# Drive_Board_2018-19.net
KiCad netlist of a schematic drawn in EAGLE
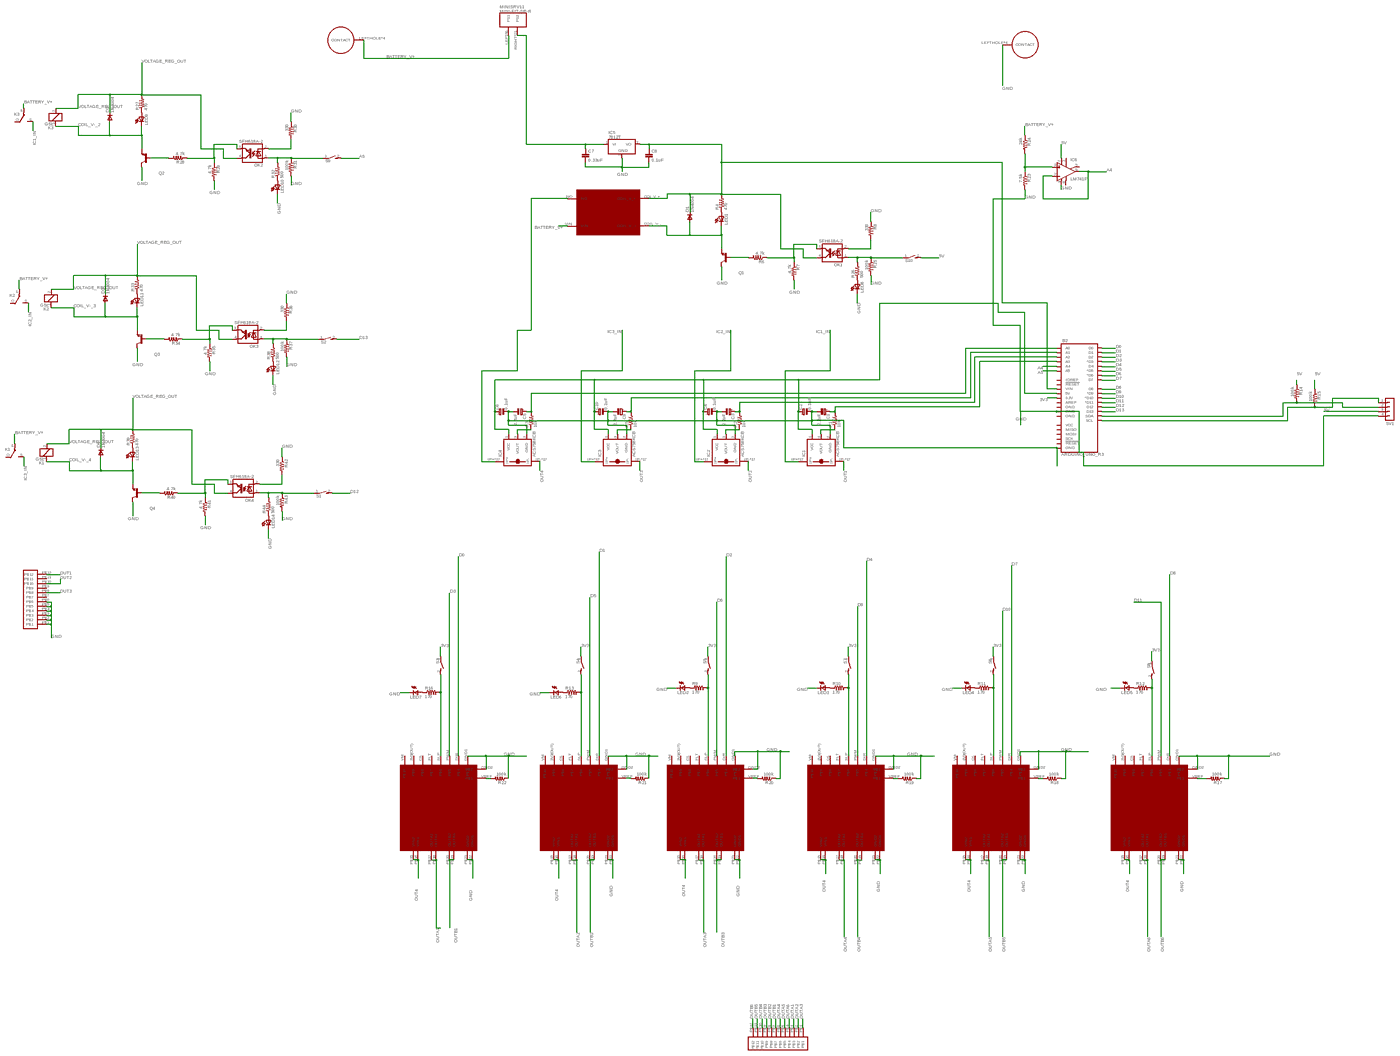
[diagram p0: schematic, sheet 1, overview]
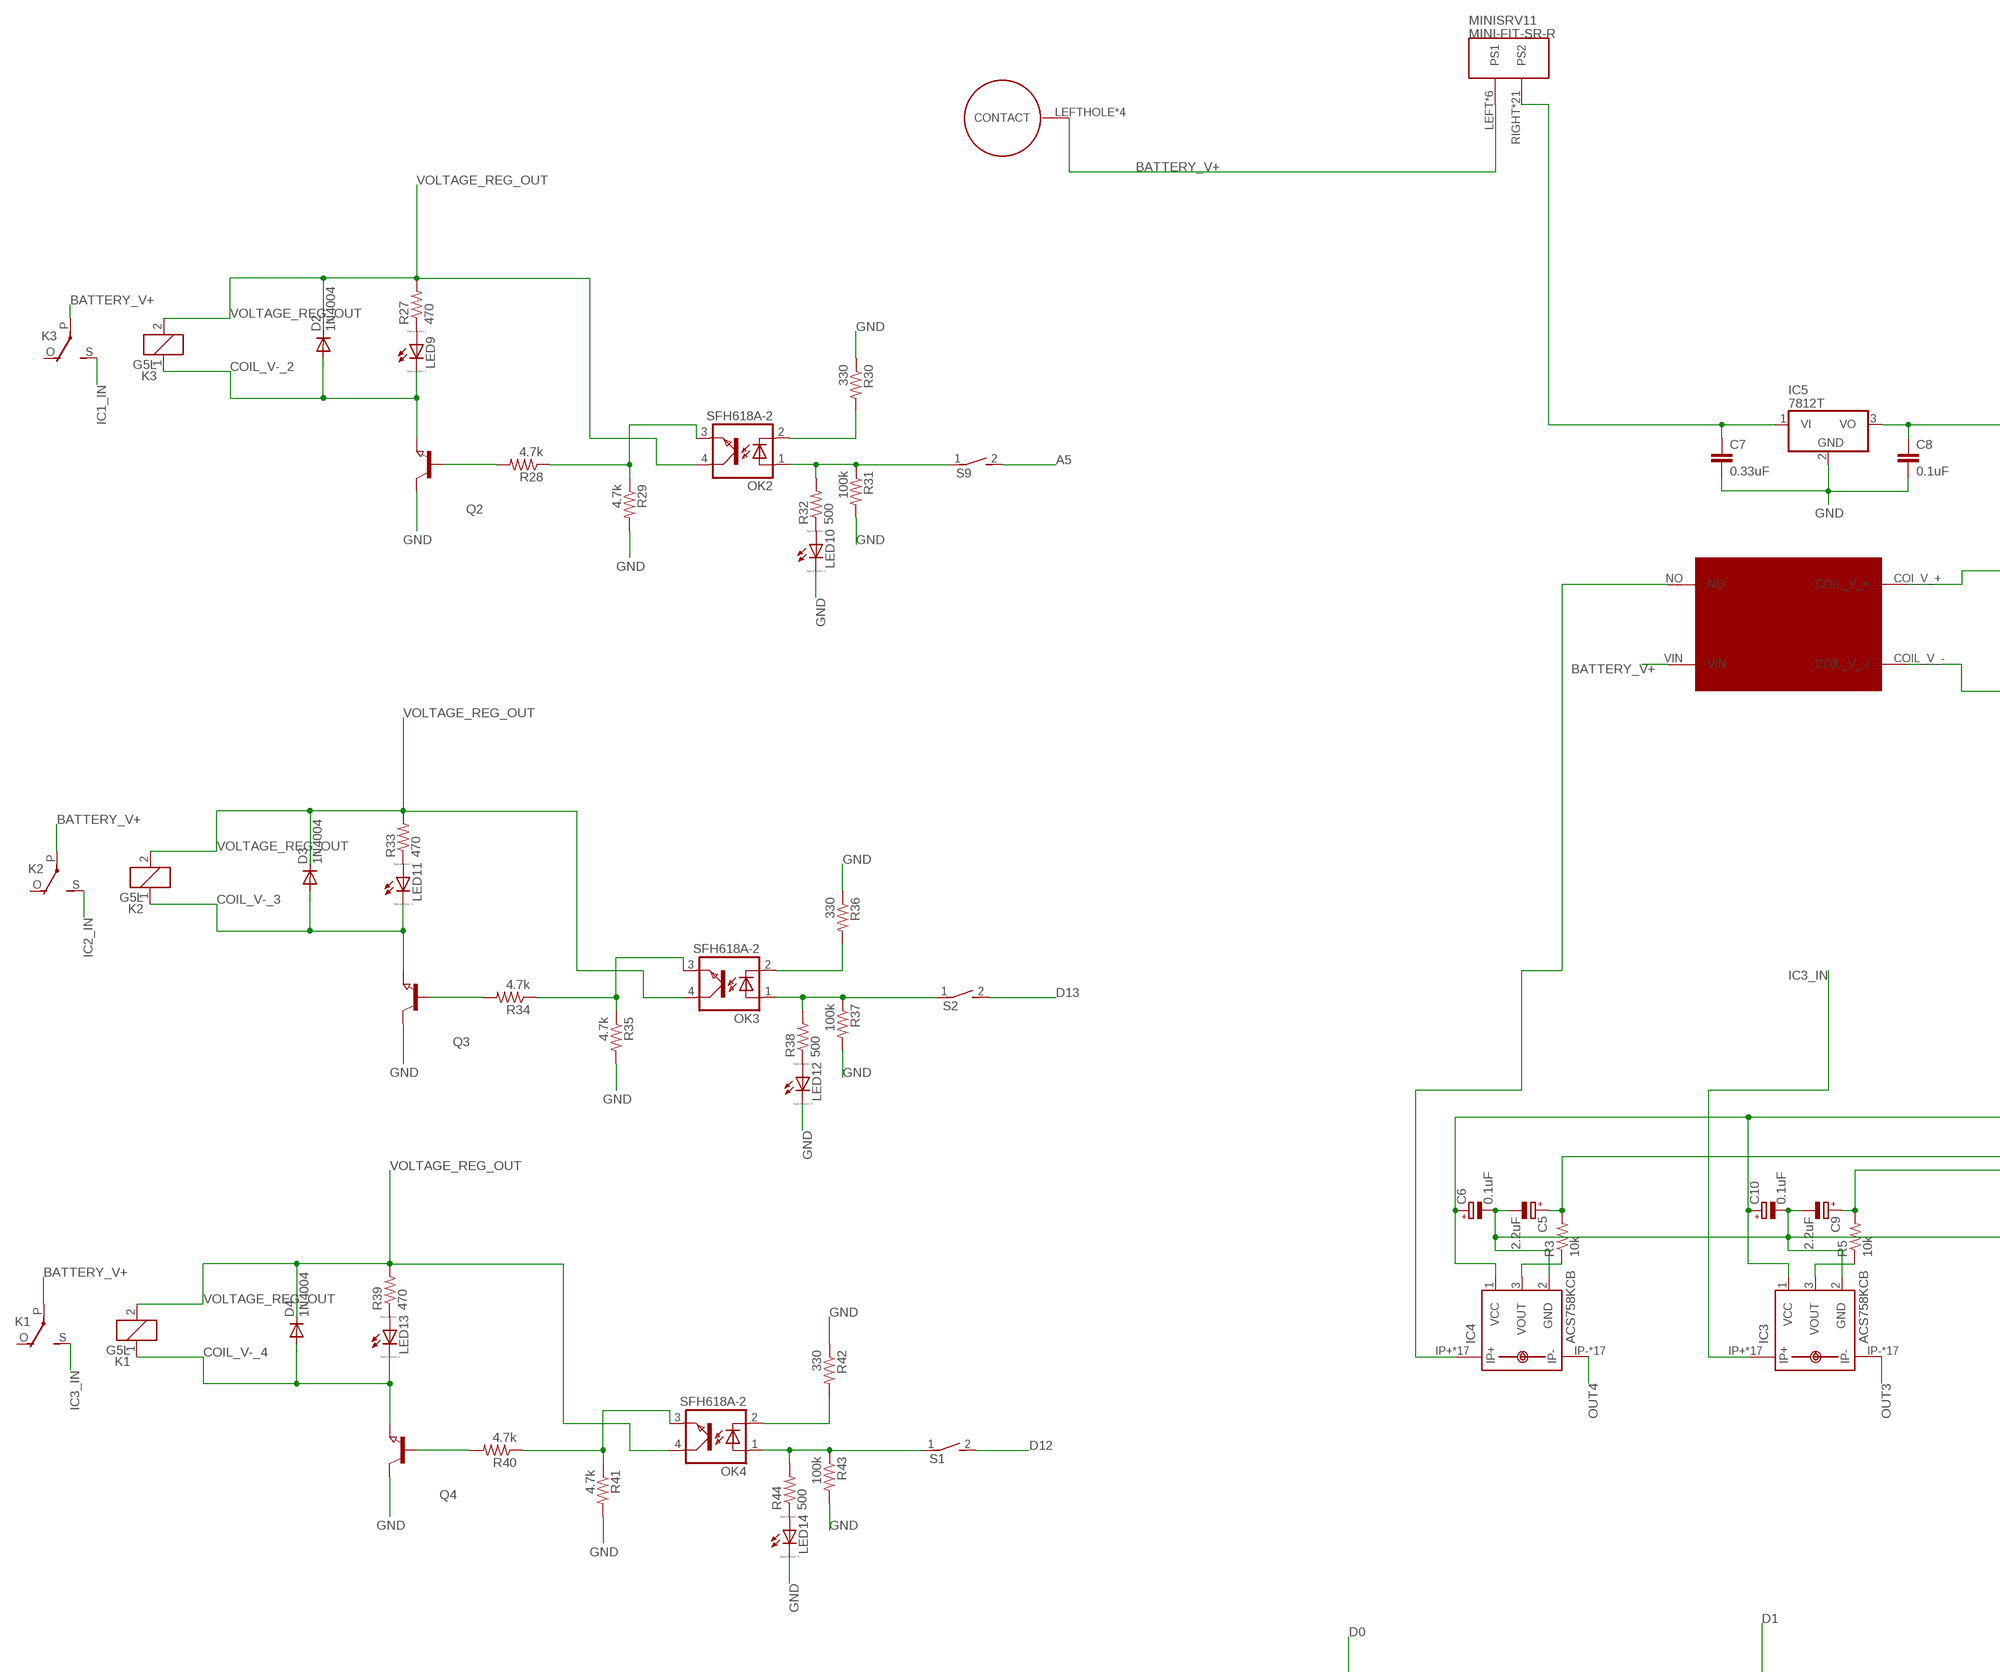
[diagram p1: schematic, sheet 1, part 1 of 4]
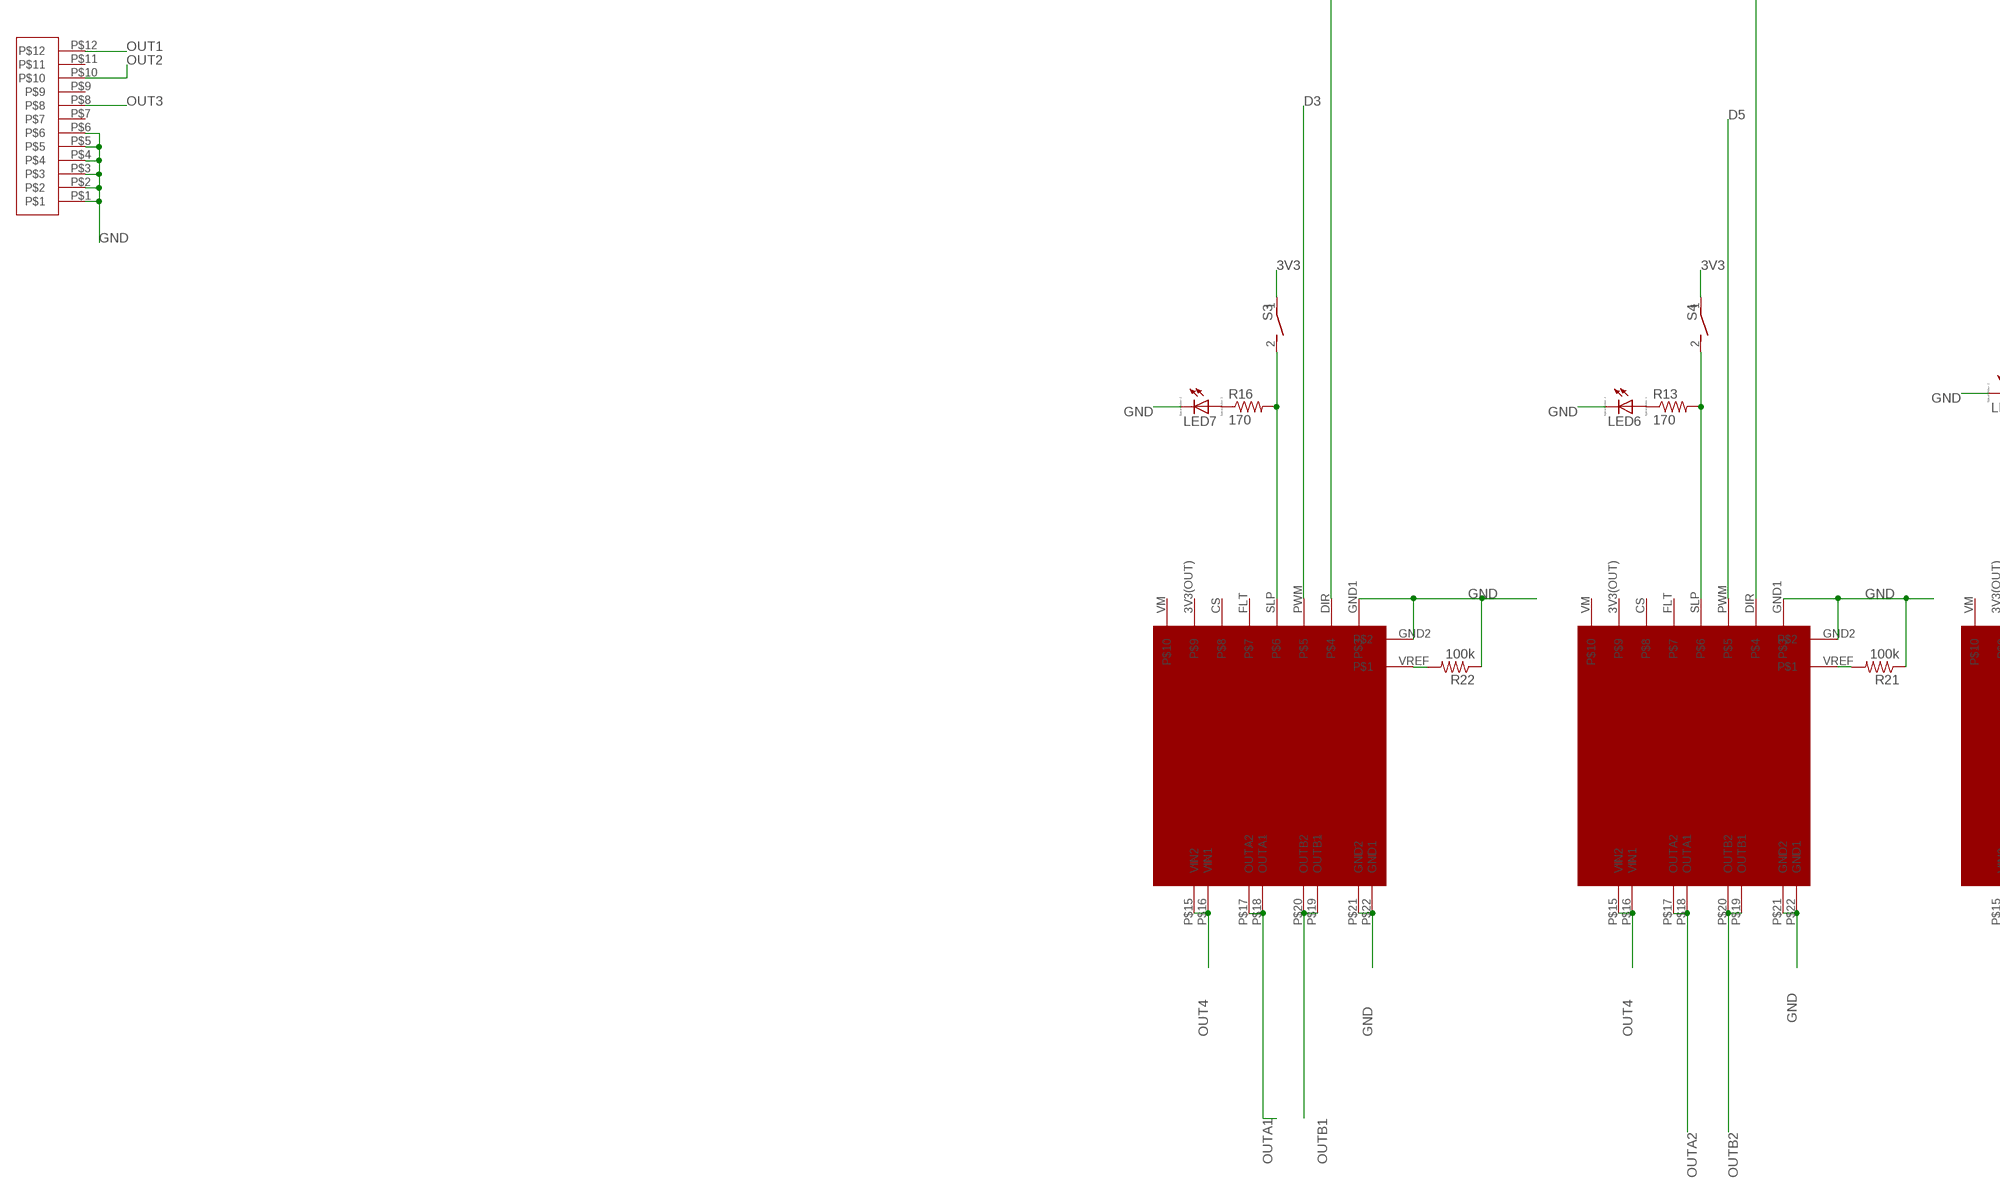
[diagram p2: schematic, sheet 1, part 2 of 4]
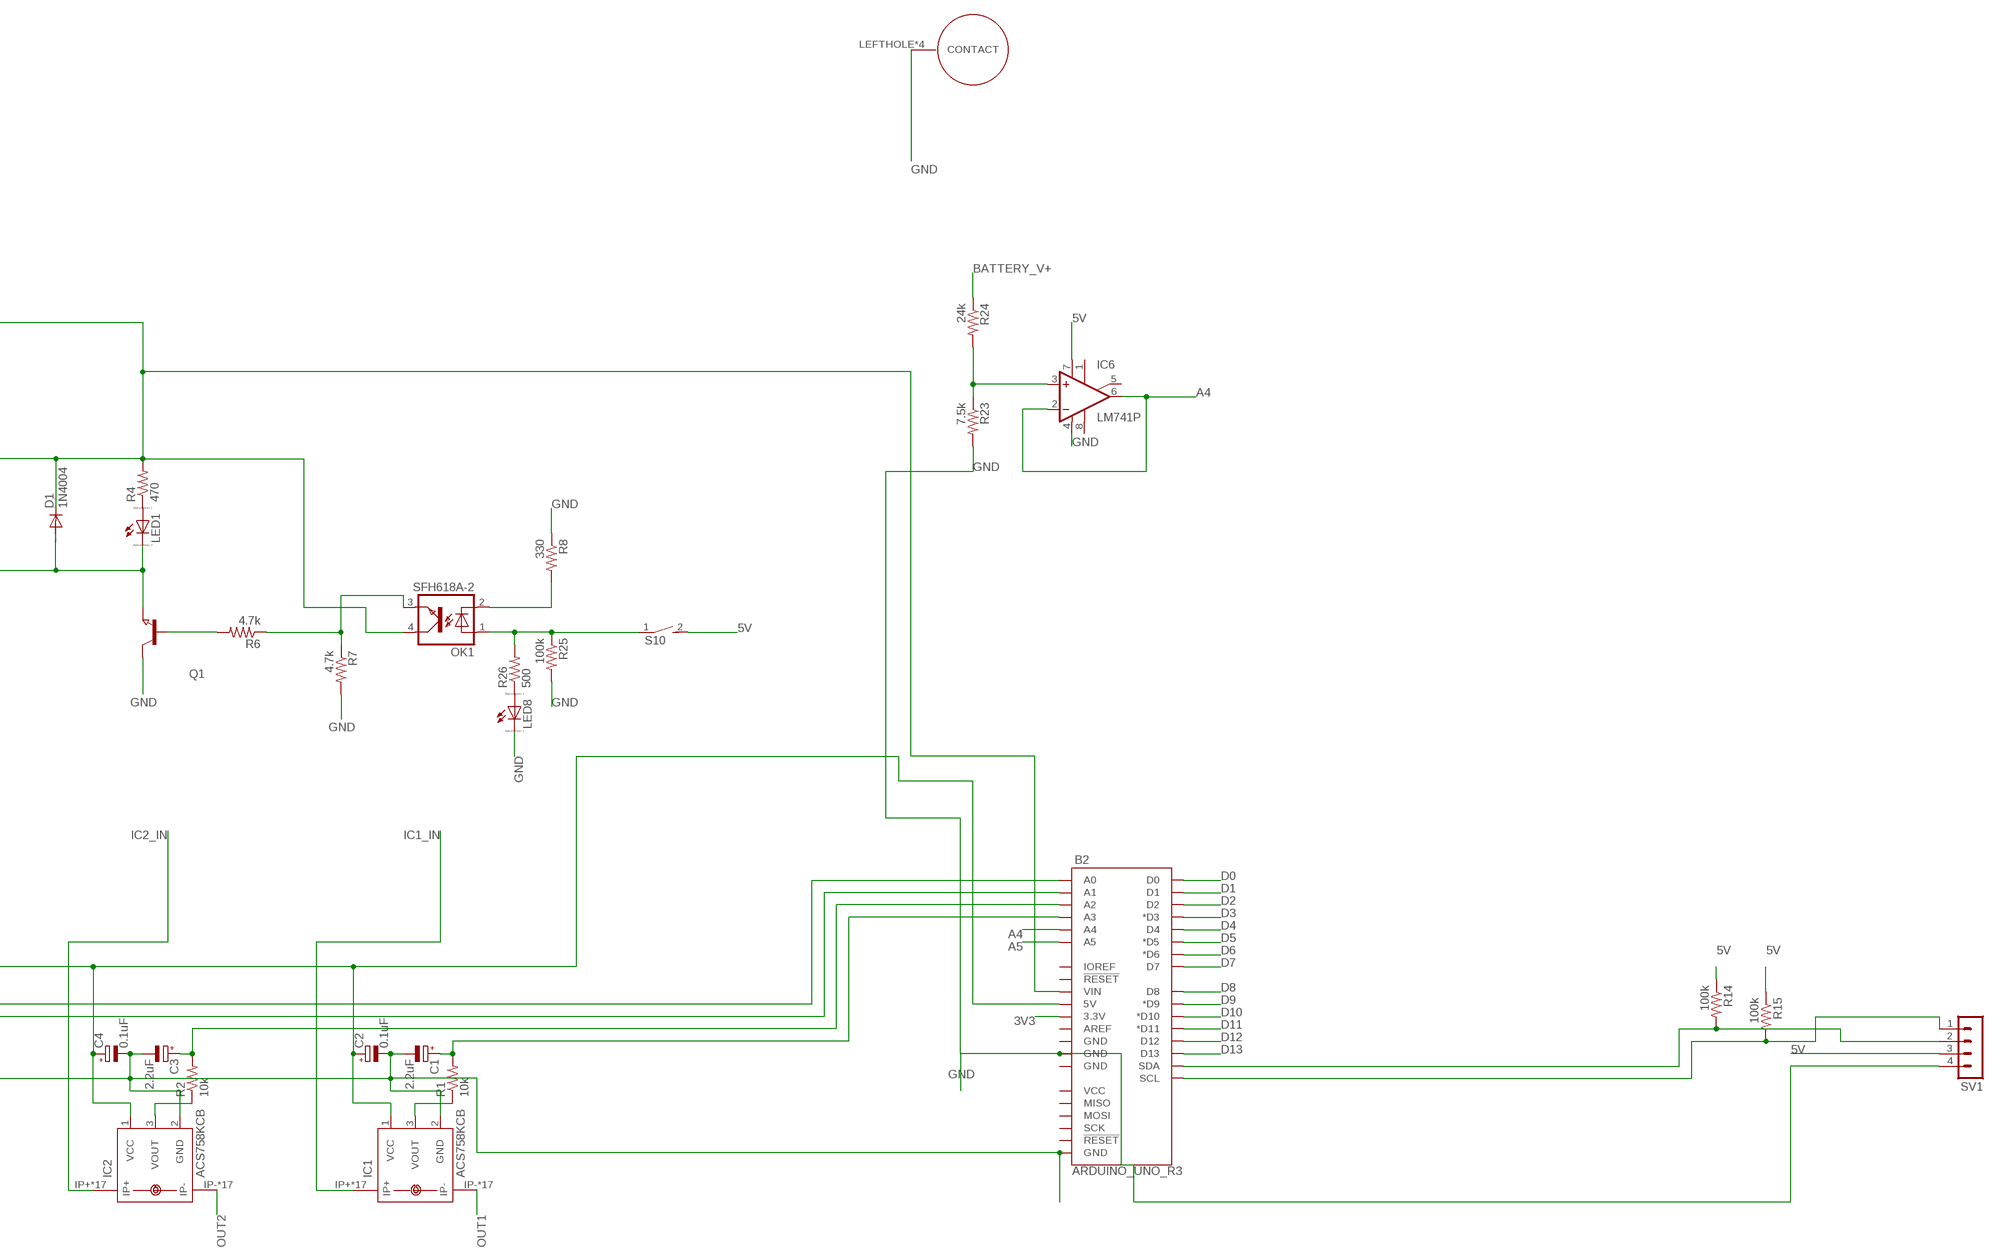
[diagram p3: schematic, sheet 1, part 3 of 4]
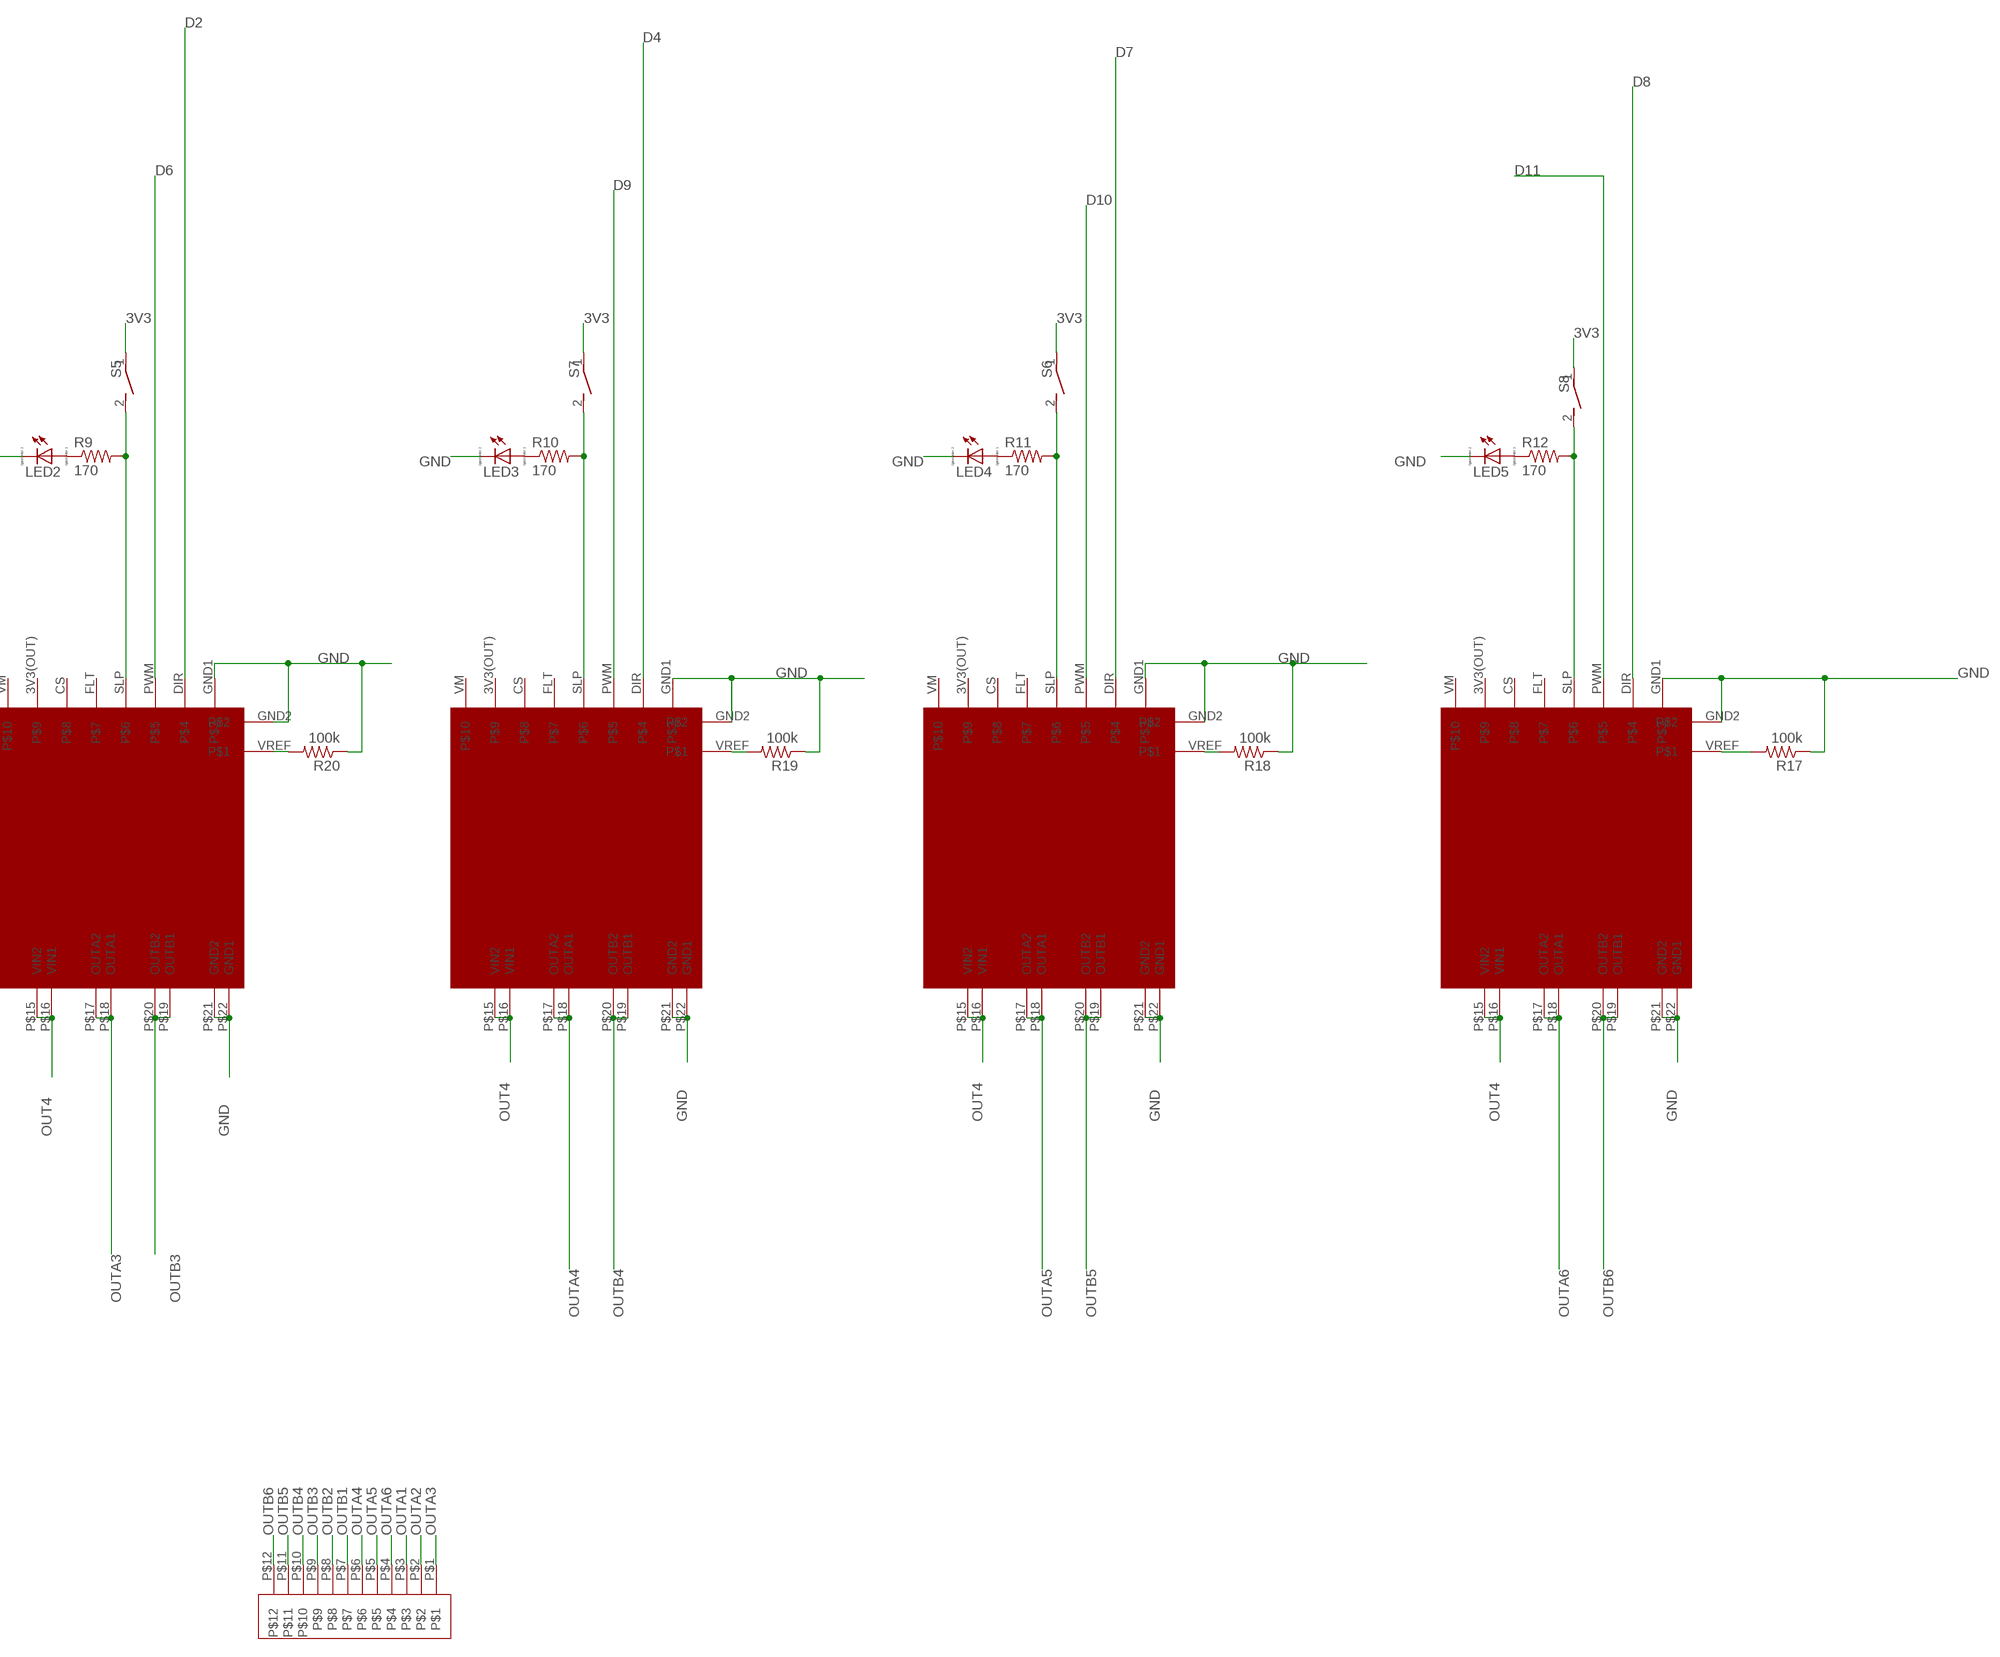
[diagram p4: schematic, sheet 1, part 4 of 4]

(export (version "E")
  (design (tool "Eeschema 10.0.6"))
  (components
    (comp (ref "B2")
      (value "ARDUINO_UNO_R3")
      (footprint "eagle-import:ARDUINO_R3")
      (libsource (lib "eagle-import") (part "ARDUINO_UNO_R3"))
    )
    (comp (ref "C1")
      (value "2.2uF")
      (footprint "eagle-import:E2,5-6")
      (libsource (lib "eagle-import") (part "CPOL-EUE2.5-6"))
    )
    (comp (ref "C2")
      (value "0.1uF")
      (footprint "eagle-import:E2,5-6")
      (libsource (lib "eagle-import") (part "CPOL-EUE2.5-6"))
    )
    (comp (ref "C3")
      (value "2.2uF")
      (footprint "eagle-import:E2,5-6")
      (libsource (lib "eagle-import") (part "CPOL-EUE2.5-6"))
    )
    (comp (ref "C4")
      (value "0.1uF")
      (footprint "eagle-import:E2,5-6")
      (libsource (lib "eagle-import") (part "CPOL-EUE2.5-6"))
    )
    (comp (ref "C5")
      (value "2.2uF")
      (footprint "eagle-import:E2,5-6")
      (libsource (lib "eagle-import") (part "CPOL-EUE2.5-6"))
    )
    (comp (ref "C6")
      (value "0.1uF")
      (footprint "eagle-import:E2,5-6")
      (libsource (lib "eagle-import") (part "CPOL-EUE2.5-6"))
    )
    (comp (ref "C7")
      (value "0.33uF")
      (footprint "eagle-import:C5B5.5")
      (libsource (lib "eagle-import") (part "C5/5.5"))
    )
    (comp (ref "C8")
      (value "0.1uF")
      (footprint "eagle-import:C5B5.5")
      (libsource (lib "eagle-import") (part "C5/5.5"))
    )
    (comp (ref "C9")
      (value "2.2uF")
      (footprint "eagle-import:E2,5-6")
      (libsource (lib "eagle-import") (part "CPOL-EUE2.5-6"))
    )
    (comp (ref "C10")
      (value "0.1uF")
      (footprint "eagle-import:E2,5-6")
      (libsource (lib "eagle-import") (part "CPOL-EUE2.5-6"))
    )
    (comp (ref "D1")
      (value "1N4004")
      (footprint "eagle-import:DO41-10")
      (libsource (lib "eagle-import") (part "1N4004"))
    )
    (comp (ref "D2")
      (value "1N4004")
      (footprint "eagle-import:DO41-10")
      (libsource (lib "eagle-import") (part "1N4004"))
    )
    (comp (ref "D3")
      (value "1N4004")
      (footprint "eagle-import:DO41-10")
      (libsource (lib "eagle-import") (part "1N4004"))
    )
    (comp (ref "D4")
      (value "1N4004")
      (footprint "eagle-import:DO41-10")
      (libsource (lib "eagle-import") (part "1N4004"))
    )
    (comp (ref "IC1")
      (value "ACS758KCB")
      (footprint "eagle-import:CB-PFF")
      (fields (field (name "MPN") "ACS758KCB-150B-PFF-T"))
      (libsource (lib "eagle-import") (part "ACS758KCB-150B-PFF-T"))
    )
    (comp (ref "IC2")
      (value "ACS758KCB")
      (footprint "eagle-import:CB-PFF")
      (fields (field (name "MPN") "ACS758KCB-150B-PFF-T"))
      (libsource (lib "eagle-import") (part "ACS758KCB-150B-PFF-T"))
    )
    (comp (ref "IC3")
      (value "ACS758KCB")
      (footprint "eagle-import:CB-PFF")
      (fields (field (name "MPN") "ACS758KCB-150B-PFF-T"))
      (libsource (lib "eagle-import") (part "ACS758KCB-150B-PFF-T"))
    )
    (comp (ref "IC4")
      (value "ACS758KCB")
      (footprint "eagle-import:CB-PFF")
      (fields (field (name "MPN") "ACS758KCB-150B-PFF-T"))
      (libsource (lib "eagle-import") (part "ACS758KCB-150B-PFF-T"))
    )
    (comp (ref "IC5")
      (value "7812T")
      (footprint "eagle-import:TO220H")
      (libsource (lib "eagle-import") (part "78T12"))
    )
    (comp (ref "IC6")
      (value "LM741P")
      (footprint "eagle-import:DIL08")
      (libsource (lib "eagle-import") (part "741PLM"))
    )
    (comp (ref "K1")
      (value "G5L")
      (footprint "eagle-import:G5LE")
      (libsource (lib "eagle-import") (part "G5L"))
    )
    (comp (ref "K2")
      (value "G5L")
      (footprint "eagle-import:G5LE")
      (libsource (lib "eagle-import") (part "G5L"))
    )
    (comp (ref "K3")
      (value "G5L")
      (footprint "eagle-import:G5LE")
      (libsource (lib "eagle-import") (part "G5L"))
    )
    (comp (ref "LED1")
      (value "LED_E")
      (footprint "eagle-import:LED_1206")
      (libsource (lib "eagle-import") (part "LED_E"))
    )
    (comp (ref "LED2")
      (value "LED_E")
      (footprint "eagle-import:LED_1206")
      (libsource (lib "eagle-import") (part "LED_E"))
    )
    (comp (ref "LED3")
      (value "LED_E")
      (footprint "eagle-import:LED_1206")
      (libsource (lib "eagle-import") (part "LED_E"))
    )
    (comp (ref "LED4")
      (value "LED_E")
      (footprint "eagle-import:LED_1206")
      (libsource (lib "eagle-import") (part "LED_E"))
    )
    (comp (ref "LED5")
      (value "LED_E")
      (footprint "eagle-import:LED_1206")
      (libsource (lib "eagle-import") (part "LED_E"))
    )
    (comp (ref "LED6")
      (value "LED_E")
      (footprint "eagle-import:LED_1206")
      (libsource (lib "eagle-import") (part "LED_E"))
    )
    (comp (ref "LED7")
      (value "LED_E")
      (footprint "eagle-import:LED_1206")
      (libsource (lib "eagle-import") (part "LED_E"))
    )
    (comp (ref "LED8")
      (value "LED_E")
      (footprint "eagle-import:LED_1206")
      (libsource (lib "eagle-import") (part "LED_E"))
    )
    (comp (ref "LED9")
      (value "LED_E")
      (footprint "eagle-import:LED_1206")
      (libsource (lib "eagle-import") (part "LED_E"))
    )
    (comp (ref "LED10")
      (value "LED_E")
      (footprint "eagle-import:LED_1206")
      (libsource (lib "eagle-import") (part "LED_E"))
    )
    (comp (ref "LED11")
      (value "LED_E")
      (footprint "eagle-import:LED_1206")
      (libsource (lib "eagle-import") (part "LED_E"))
    )
    (comp (ref "LED12")
      (value "LED_E")
      (footprint "eagle-import:LED_1206")
      (libsource (lib "eagle-import") (part "LED_E"))
    )
    (comp (ref "LED13")
      (value "LED_E")
      (footprint "eagle-import:LED_1206")
      (libsource (lib "eagle-import") (part "LED_E"))
    )
    (comp (ref "LED14")
      (value "LED_E")
      (footprint "eagle-import:LED_1206")
      (libsource (lib "eagle-import") (part "LED_E"))
    )
    (comp (ref "MINISRV11")
      (value "MINI-FIT-SR-R")
      (footprint "eagle-import:MINI-FIT-SR-R")
      (libsource (lib "eagle-import") (part "MINI-FIT-SR-R"))
    )
    (comp (ref "OK1")
      (value "SFH618A-2")
      (footprint "eagle-import:DIP4")
      (fields (field (name "MF") "VISHAY/TELEFUNKEN"))
      (libsource (lib "eagle-import") (part "SFH618?A-2"))
    )
    (comp (ref "OK2")
      (value "SFH618A-2")
      (footprint "eagle-import:DIP4")
      (fields (field (name "MF") "VISHAY/TELEFUNKEN"))
      (libsource (lib "eagle-import") (part "SFH618?A-2"))
    )
    (comp (ref "OK3")
      (value "SFH618A-2")
      (footprint "eagle-import:DIP4")
      (fields (field (name "MF") "VISHAY/TELEFUNKEN"))
      (libsource (lib "eagle-import") (part "SFH618?A-2"))
    )
    (comp (ref "OK4")
      (value "SFH618A-2")
      (footprint "eagle-import:DIP4")
      (fields (field (name "MF") "VISHAY/TELEFUNKEN"))
      (libsource (lib "eagle-import") (part "SFH618?A-2"))
    )
    (comp (ref "Q1")
      (value "NPN-TRANSISTOR_SOT23")
      (footprint "eagle-import:SOT23")
      (libsource (lib "eagle-import") (part "NPN-TRANSISTOR_SOT23"))
    )
    (comp (ref "Q2")
      (value "NPN-TRANSISTOR_SOT23")
      (footprint "eagle-import:SOT23")
      (libsource (lib "eagle-import") (part "NPN-TRANSISTOR_SOT23"))
    )
    (comp (ref "Q3")
      (value "NPN-TRANSISTOR_SOT23")
      (footprint "eagle-import:SOT23")
      (libsource (lib "eagle-import") (part "NPN-TRANSISTOR_SOT23"))
    )
    (comp (ref "Q4")
      (value "NPN-TRANSISTOR_SOT23")
      (footprint "eagle-import:SOT23")
      (libsource (lib "eagle-import") (part "NPN-TRANSISTOR_SOT23"))
    )
    (comp (ref "R1")
      (value "10k")
      (footprint "eagle-import:0204_7")
      (libsource (lib "eagle-import") (part "R-US_0204/7"))
    )
    (comp (ref "R2")
      (value "10k")
      (footprint "eagle-import:0204_7")
      (libsource (lib "eagle-import") (part "R-US_0204/7"))
    )
    (comp (ref "R3")
      (value "10k")
      (footprint "eagle-import:0204_7")
      (libsource (lib "eagle-import") (part "R-US_0204/7"))
    )
    (comp (ref "R4")
      (value "470")
      (footprint "eagle-import:0207_10")
      (libsource (lib "eagle-import") (part "R-US_0207/10"))
    )
    (comp (ref "R5")
      (value "10k")
      (footprint "eagle-import:0204_7")
      (libsource (lib "eagle-import") (part "R-US_0204/7"))
    )
    (comp (ref "R6")
      (value "4.7k")
      (footprint "eagle-import:0207_10")
      (libsource (lib "eagle-import") (part "R-US_0207/10"))
    )
    (comp (ref "R7")
      (value "4.7k")
      (footprint "eagle-import:0207_10")
      (libsource (lib "eagle-import") (part "R-US_0207/10"))
    )
    (comp (ref "R8")
      (value "330")
      (footprint "eagle-import:0207_10")
      (libsource (lib "eagle-import") (part "R-US_0207/10"))
    )
    (comp (ref "R9")
      (value "170")
      (footprint "eagle-import:0207_10")
      (libsource (lib "eagle-import") (part "R-US_0207/10"))
    )
    (comp (ref "R10")
      (value "170")
      (footprint "eagle-import:0207_10")
      (libsource (lib "eagle-import") (part "R-US_0207/10"))
    )
    (comp (ref "R11")
      (value "170")
      (footprint "eagle-import:0207_10")
      (libsource (lib "eagle-import") (part "R-US_0207/10"))
    )
    (comp (ref "R12")
      (value "170")
      (footprint "eagle-import:0207_10")
      (libsource (lib "eagle-import") (part "R-US_0207/10"))
    )
    (comp (ref "R13")
      (value "170")
      (footprint "eagle-import:0207_10")
      (libsource (lib "eagle-import") (part "R-US_0207/10"))
    )
    (comp (ref "R14")
      (value "100k")
      (footprint "eagle-import:0207_10")
      (libsource (lib "eagle-import") (part "R-US_0207/10"))
    )
    (comp (ref "R15")
      (value "100k")
      (footprint "eagle-import:0207_10")
      (libsource (lib "eagle-import") (part "R-US_0207/10"))
    )
    (comp (ref "R16")
      (value "170")
      (footprint "eagle-import:0207_10")
      (libsource (lib "eagle-import") (part "R-US_0207/10"))
    )
    (comp (ref "R17")
      (value "100k")
      (footprint "eagle-import:0207_10")
      (libsource (lib "eagle-import") (part "R-US_0207/10"))
    )
    (comp (ref "R18")
      (value "100k")
      (footprint "eagle-import:0207_10")
      (libsource (lib "eagle-import") (part "R-US_0207/10"))
    )
    (comp (ref "R19")
      (value "100k")
      (footprint "eagle-import:0207_10")
      (libsource (lib "eagle-import") (part "R-US_0207/10"))
    )
    (comp (ref "R20")
      (value "100k")
      (footprint "eagle-import:0207_10")
      (libsource (lib "eagle-import") (part "R-US_0207/10"))
    )
    (comp (ref "R21")
      (value "100k")
      (footprint "eagle-import:0207_10")
      (libsource (lib "eagle-import") (part "R-US_0207/10"))
    )
    (comp (ref "R22")
      (value "100k")
      (footprint "eagle-import:0207_10")
      (libsource (lib "eagle-import") (part "R-US_0207/10"))
    )
    (comp (ref "R23")
      (value "7.5k")
      (footprint "eagle-import:0207_10")
      (libsource (lib "eagle-import") (part "R-US_0207/10"))
    )
    (comp (ref "R24")
      (value "24k")
      (footprint "eagle-import:0207_10")
      (libsource (lib "eagle-import") (part "R-US_0207/10"))
    )
    (comp (ref "R25")
      (value "100k")
      (footprint "eagle-import:0207_10")
      (libsource (lib "eagle-import") (part "R-US_0207/10"))
    )
    (comp (ref "R26")
      (value "500")
      (footprint "eagle-import:0207_10")
      (libsource (lib "eagle-import") (part "R-US_0207/10"))
    )
    (comp (ref "R27")
      (value "470")
      (footprint "eagle-import:0207_10")
      (libsource (lib "eagle-import") (part "R-US_0207/10"))
    )
    (comp (ref "R28")
      (value "4.7k")
      (footprint "eagle-import:0207_10")
      (libsource (lib "eagle-import") (part "R-US_0207/10"))
    )
    (comp (ref "R29")
      (value "4.7k")
      (footprint "eagle-import:0207_10")
      (libsource (lib "eagle-import") (part "R-US_0207/10"))
    )
    (comp (ref "R30")
      (value "330")
      (footprint "eagle-import:0207_10")
      (libsource (lib "eagle-import") (part "R-US_0207/10"))
    )
    (comp (ref "R31")
      (value "100k")
      (footprint "eagle-import:0207_10")
      (libsource (lib "eagle-import") (part "R-US_0207/10"))
    )
    (comp (ref "R32")
      (value "500")
      (footprint "eagle-import:0207_10")
      (libsource (lib "eagle-import") (part "R-US_0207/10"))
    )
    (comp (ref "R33")
      (value "470")
      (footprint "eagle-import:0207_10")
      (libsource (lib "eagle-import") (part "R-US_0207/10"))
    )
    (comp (ref "R34")
      (value "4.7k")
      (footprint "eagle-import:0207_10")
      (libsource (lib "eagle-import") (part "R-US_0207/10"))
    )
    (comp (ref "R35")
      (value "4.7k")
      (footprint "eagle-import:0207_10")
      (libsource (lib "eagle-import") (part "R-US_0207/10"))
    )
    (comp (ref "R36")
      (value "330")
      (footprint "eagle-import:0207_10")
      (libsource (lib "eagle-import") (part "R-US_0207/10"))
    )
    (comp (ref "R37")
      (value "100k")
      (footprint "eagle-import:0207_10")
      (libsource (lib "eagle-import") (part "R-US_0207/10"))
    )
    (comp (ref "R38")
      (value "500")
      (footprint "eagle-import:0207_10")
      (libsource (lib "eagle-import") (part "R-US_0207/10"))
    )
    (comp (ref "R39")
      (value "470")
      (footprint "eagle-import:0207_10")
      (libsource (lib "eagle-import") (part "R-US_0207/10"))
    )
    (comp (ref "R40")
      (value "4.7k")
      (footprint "eagle-import:0207_10")
      (libsource (lib "eagle-import") (part "R-US_0207/10"))
    )
    (comp (ref "R41")
      (value "4.7k")
      (footprint "eagle-import:0207_10")
      (libsource (lib "eagle-import") (part "R-US_0207/10"))
    )
    (comp (ref "R42")
      (value "330")
      (footprint "eagle-import:0207_10")
      (libsource (lib "eagle-import") (part "R-US_0207/10"))
    )
    (comp (ref "R43")
      (value "100k")
      (footprint "eagle-import:0207_10")
      (libsource (lib "eagle-import") (part "R-US_0207/10"))
    )
    (comp (ref "R44")
      (value "500")
      (footprint "eagle-import:0207_10")
      (libsource (lib "eagle-import") (part "R-US_0207/10"))
    )
    (comp (ref "S1")
      (value "DS01E")
      (footprint "eagle-import:DS-01")
      (libsource (lib "eagle-import") (part "DS01E"))
    )
    (comp (ref "S2")
      (value "DS01E")
      (footprint "eagle-import:DS-01")
      (libsource (lib "eagle-import") (part "DS01E"))
    )
    (comp (ref "S3")
      (value "DS01E")
      (footprint "eagle-import:DS-01")
      (libsource (lib "eagle-import") (part "DS01E"))
    )
    (comp (ref "S4")
      (value "DS01E")
      (footprint "eagle-import:DS-01")
      (libsource (lib "eagle-import") (part "DS01E"))
    )
    (comp (ref "S5")
      (value "DS01E")
      (footprint "eagle-import:DS-01")
      (libsource (lib "eagle-import") (part "DS01E"))
    )
    (comp (ref "S6")
      (value "DS01E")
      (footprint "eagle-import:DS-01")
      (libsource (lib "eagle-import") (part "DS01E"))
    )
    (comp (ref "S7")
      (value "DS01E")
      (footprint "eagle-import:DS-01")
      (libsource (lib "eagle-import") (part "DS01E"))
    )
    (comp (ref "S8")
      (value "DS01E")
      (footprint "eagle-import:DS-01")
      (libsource (lib "eagle-import") (part "DS01E"))
    )
    (comp (ref "S9")
      (value "DS01E")
      (footprint "eagle-import:DS-01")
      (libsource (lib "eagle-import") (part "DS01E"))
    )
    (comp (ref "S10")
      (value "DS01E")
      (footprint "eagle-import:DS-01")
      (libsource (lib "eagle-import") (part "DS01E"))
    )
    (comp (ref "SV1")
      (value "MA04-1")
      (footprint "eagle-import:MA04-1")
      (libsource (lib "eagle-import") (part "MA04-1"))
    )
    (comp (ref "U$1")
      (value "HPMD18V17")
      (footprint "eagle-import:HPMD18V17")
      (libsource (lib "eagle-import") (part "HPMD18V17"))
    )
    (comp (ref "U$2")
      (value "HPMD18V17")
      (footprint "eagle-import:HPMD18V17")
      (libsource (lib "eagle-import") (part "HPMD18V17"))
    )
    (comp (ref "U$3")
      (value "HPMD18V17")
      (footprint "eagle-import:HPMD18V17")
      (libsource (lib "eagle-import") (part "HPMD18V17"))
    )
    (comp (ref "U$4")
      (value "HPMD18V17")
      (footprint "eagle-import:HPMD18V17")
      (libsource (lib "eagle-import") (part "HPMD18V17"))
    )
    (comp (ref "U$5")
      (value "HPMD18V17")
      (footprint "eagle-import:HPMD18V17")
      (libsource (lib "eagle-import") (part "HPMD18V17"))
    )
    (comp (ref "U$6")
      (value "HPMD18V17")
      (footprint "eagle-import:HPMD18V17")
      (libsource (lib "eagle-import") (part "HPMD18V17"))
    )
    (comp (ref "U$7")
      (value "BUSBAR_MOUNT")
      (footprint "eagle-import:BUSBAR_MOUNT")
      (libsource (lib "eagle-import") (part "BUSBAR_MOUNT"))
    )
    (comp (ref "U$9")
      (value "BUSBAR_MOUNT")
      (footprint "eagle-import:BUSBAR_MOUNT")
      (libsource (lib "eagle-import") (part "BUSBAR_MOUNT"))
    )
    (comp (ref "U$11")
      (value "JTN1AS-PA-F-DC12V")
      (footprint "eagle-import:JTN1AS-PA-F-DC12V")
      (libsource (lib "eagle-import") (part "JTN1AS-PA-F-DC12V"))
    )
    (comp (ref "U$12")
      (value "MEGA-FIT_RA_12")
      (footprint "eagle-import:MEGA-FIT_RA_12")
      (libsource (lib "eagle-import") (part "MEGA-FIT_RA_12"))
    )
    (comp (ref "U$13")
      (value "MEGA-FIT_RA_12")
      (footprint "eagle-import:MEGA-FIT_RA_12")
      (libsource (lib "eagle-import") (part "MEGA-FIT_RA_12"))
    )
  )
  (nets
    (net (code "1") (name "/3V3") (class "Default")
      (node (ref "B2") (pin "3.3V") (pinfunction "3.3V_3.3V") (pintype "bidirectional"))
      (node (ref "S3") (pin "1") (pinfunction "1_1") (pintype "passive"))
      (node (ref "S4") (pin "1") (pinfunction "1_1") (pintype "passive"))
      (node (ref "S5") (pin "1") (pinfunction "1_1") (pintype "passive"))
      (node (ref "S6") (pin "1") (pinfunction "1_1") (pintype "passive"))
      (node (ref "S7") (pin "1") (pinfunction "1_1") (pintype "passive"))
      (node (ref "S8") (pin "1") (pinfunction "1_1") (pintype "passive"))
    )
    (net (code "2") (name "/5V") (class "Default")
      (node (ref "B2") (pin "5V") (pinfunction "5V_5V") (pintype "bidirectional"))
      (node (ref "C10") (pin "+") (pinfunction "+_+") (pintype "passive"))
      (node (ref "C2") (pin "+") (pinfunction "+_+") (pintype "passive"))
      (node (ref "C4") (pin "+") (pinfunction "+_+") (pintype "passive"))
      (node (ref "C6") (pin "+") (pinfunction "+_+") (pintype "passive"))
      (node (ref "IC1") (pin "1") (pinfunction "VCC_1") (pintype "power_in"))
      (node (ref "IC2") (pin "1") (pinfunction "VCC_1") (pintype "power_in"))
      (node (ref "IC3") (pin "1") (pinfunction "VCC_1") (pintype "power_in"))
      (node (ref "IC4") (pin "1") (pinfunction "VCC_1") (pintype "power_in"))
      (node (ref "IC6") (pin "7") (pinfunction "V+_7") (pintype "power_in"))
      (node (ref "R14") (pin "1") (pinfunction "1_1") (pintype "passive"))
      (node (ref "R15") (pin "1") (pinfunction "1_1") (pintype "passive"))
      (node (ref "S10") (pin "2") (pinfunction "2_2") (pintype "passive"))
      (node (ref "SV1") (pin "3") (pinfunction "3_3") (pintype "passive"))
    )
    (net (code "3") (name "/A4") (class "Default")
      (node (ref "B2") (pin "A4") (pinfunction "A4_A4") (pintype "bidirectional"))
      (node (ref "IC6") (pin "2") (pinfunction "-IN_2") (pintype "input"))
      (node (ref "IC6") (pin "6") (pinfunction "OUT_6") (pintype "output"))
    )
    (net (code "4") (name "/A5") (class "Default")
      (node (ref "B2") (pin "A5") (pinfunction "A5_A5") (pintype "bidirectional"))
      (node (ref "S9") (pin "2") (pinfunction "2_2") (pintype "passive"))
    )
    (net (code "5") (name "/BATTERY_V+") (class "Default")
      (node (ref "K1") (pin "P") (pinfunction "P_P") (pintype "passive"))
      (node (ref "K2") (pin "P") (pinfunction "P_P") (pintype "passive"))
      (node (ref "K3") (pin "P") (pinfunction "P_P") (pintype "passive"))
      (node (ref "MINISRV11") (pin "LEFT") (pinfunction "PS1_LEFT") (pintype "bidirectional"))
      (node (ref "MINISRV11") (pin "LEFT@1") (pinfunction "PS1_LEFT@1") (pintype "bidirectional"))
      (node (ref "MINISRV11") (pin "LEFT@2") (pinfunction "PS1_LEFT@2") (pintype "bidirectional"))
      (node (ref "MINISRV11") (pin "LEFT@3") (pinfunction "PS1_LEFT@3") (pintype "bidirectional"))
      (node (ref "MINISRV11") (pin "LEFT@4") (pinfunction "PS1_LEFT@4") (pintype "bidirectional"))
      (node (ref "MINISRV11") (pin "LEFT@5") (pinfunction "PS1_LEFT@5") (pintype "bidirectional"))
      (node (ref "R24") (pin "1") (pinfunction "1_1") (pintype "passive"))
      (node (ref "U$11") (pin "VIN") (pinfunction "VIN_VIN") (pintype "bidirectional"))
      (node (ref "U$7") (pin "LEFTHOLE") (pinfunction "CONTACT_LEFTHOLE") (pintype "bidirectional"))
      (node (ref "U$7") (pin "P$1") (pinfunction "CONTACT_P$1") (pintype "bidirectional"))
      (node (ref "U$7") (pin "P$2") (pinfunction "CONTACT_P$2") (pintype "bidirectional"))
      (node (ref "U$7") (pin "RIGHTHOLE") (pinfunction "CONTACT_RIGHTHOLE") (pintype "bidirectional"))
    )
    (net (code "6") (name "/COIL_V-_2") (class "Default")
      (node (ref "D2") (pin "A") (pinfunction "A_A") (pintype "passive"))
      (node (ref "K3") (pin "1") (pinfunction "1_1") (pintype "passive"))
      (node (ref "LED9") (pin "C") (pinfunction "C_C") (pintype "passive"))
      (node (ref "Q2") (pin "2") (pinfunction "E_2") (pintype "passive"))
    )
    (net (code "7") (name "/COIL_V-_3") (class "Default")
      (node (ref "D3") (pin "A") (pinfunction "A_A") (pintype "passive"))
      (node (ref "K2") (pin "1") (pinfunction "1_1") (pintype "passive"))
      (node (ref "LED11") (pin "C") (pinfunction "C_C") (pintype "passive"))
      (node (ref "Q3") (pin "2") (pinfunction "E_2") (pintype "passive"))
    )
    (net (code "8") (name "/COIL_V-_4") (class "Default")
      (node (ref "D4") (pin "A") (pinfunction "A_A") (pintype "passive"))
      (node (ref "K1") (pin "1") (pinfunction "1_1") (pintype "passive"))
      (node (ref "LED13") (pin "C") (pinfunction "C_C") (pintype "passive"))
      (node (ref "Q4") (pin "2") (pinfunction "E_2") (pintype "passive"))
    )
    (net (code "9") (name "/D0") (class "Default")
      (node (ref "B2") (pin "D0") (pinfunction "D0_D0") (pintype "bidirectional"))
      (node (ref "U$1") (pin "DIR") (pinfunction "P$4_DIR") (pintype "bidirectional"))
    )
    (net (code "10") (name "/D1") (class "Default")
      (node (ref "B2") (pin "D1") (pinfunction "D1_D1") (pintype "bidirectional"))
      (node (ref "U$2") (pin "DIR") (pinfunction "P$4_DIR") (pintype "bidirectional"))
    )
    (net (code "11") (name "/D2") (class "Default")
      (node (ref "B2") (pin "D2") (pinfunction "D2_D2") (pintype "bidirectional"))
      (node (ref "U$3") (pin "DIR") (pinfunction "P$4_DIR") (pintype "bidirectional"))
    )
    (net (code "12") (name "/D3") (class "Default")
      (node (ref "B2") (pin "D3") (pinfunction "*D3_D3") (pintype "bidirectional"))
      (node (ref "U$1") (pin "PWM") (pinfunction "P$5_PWM") (pintype "bidirectional"))
    )
    (net (code "13") (name "/D4") (class "Default")
      (node (ref "B2") (pin "D4") (pinfunction "D4_D4") (pintype "bidirectional"))
      (node (ref "U$4") (pin "DIR") (pinfunction "P$4_DIR") (pintype "bidirectional"))
    )
    (net (code "14") (name "/D5") (class "Default")
      (node (ref "B2") (pin "D5") (pinfunction "*D5_D5") (pintype "bidirectional"))
      (node (ref "U$2") (pin "PWM") (pinfunction "P$5_PWM") (pintype "bidirectional"))
    )
    (net (code "15") (name "/D6") (class "Default")
      (node (ref "B2") (pin "D6") (pinfunction "*D6_D6") (pintype "bidirectional"))
      (node (ref "U$3") (pin "PWM") (pinfunction "P$5_PWM") (pintype "bidirectional"))
    )
    (net (code "16") (name "/D7") (class "Default")
      (node (ref "B2") (pin "D7") (pinfunction "D7_D7") (pintype "bidirectional"))
      (node (ref "U$5") (pin "DIR") (pinfunction "P$4_DIR") (pintype "bidirectional"))
    )
    (net (code "17") (name "/D8") (class "Default")
      (node (ref "B2") (pin "D8") (pinfunction "D8_D8") (pintype "bidirectional"))
      (node (ref "U$6") (pin "DIR") (pinfunction "P$4_DIR") (pintype "bidirectional"))
    )
    (net (code "18") (name "/D9") (class "Default")
      (node (ref "B2") (pin "D9") (pinfunction "*D9_D9") (pintype "bidirectional"))
      (node (ref "U$4") (pin "PWM") (pinfunction "P$5_PWM") (pintype "bidirectional"))
    )
    (net (code "19") (name "/D10") (class "Default")
      (node (ref "B2") (pin "D10") (pinfunction "*D10_D10") (pintype "bidirectional"))
      (node (ref "U$5") (pin "PWM") (pinfunction "P$5_PWM") (pintype "bidirectional"))
    )
    (net (code "20") (name "/D11") (class "Default")
      (node (ref "B2") (pin "D11") (pinfunction "*D11_D11") (pintype "bidirectional"))
      (node (ref "U$6") (pin "PWM") (pinfunction "P$5_PWM") (pintype "bidirectional"))
    )
    (net (code "21") (name "/D12") (class "Default")
      (node (ref "B2") (pin "D12") (pinfunction "D12_D12") (pintype "bidirectional"))
      (node (ref "S1") (pin "2") (pinfunction "2_2") (pintype "passive"))
    )
    (net (code "22") (name "/D13") (class "Default")
      (node (ref "B2") (pin "D13") (pinfunction "D13_D13") (pintype "bidirectional"))
      (node (ref "S2") (pin "2") (pinfunction "2_2") (pintype "passive"))
    )
    (net (code "23") (name "/GND") (class "Default")
      (node (ref "B2") (pin "GND@1") (pinfunction "GND_GND@1") (pintype "bidirectional"))
      (node (ref "B2") (pin "GND@3") (pinfunction "GND_GND@3") (pintype "bidirectional"))
      (node (ref "C1") (pin "-") (pinfunction "-_-") (pintype "passive"))
      (node (ref "C10") (pin "-") (pinfunction "-_-") (pintype "passive"))
      (node (ref "C2") (pin "-") (pinfunction "-_-") (pintype "passive"))
      (node (ref "C3") (pin "-") (pinfunction "-_-") (pintype "passive"))
      (node (ref "C4") (pin "-") (pinfunction "-_-") (pintype "passive"))
      (node (ref "C5") (pin "-") (pinfunction "-_-") (pintype "passive"))
      (node (ref "C6") (pin "-") (pinfunction "-_-") (pintype "passive"))
      (node (ref "C7") (pin "2") (pinfunction "2_2") (pintype "passive"))
      (node (ref "C8") (pin "2") (pinfunction "2_2") (pintype "passive"))
      (node (ref "C9") (pin "-") (pinfunction "-_-") (pintype "passive"))
      (node (ref "IC1") (pin "2") (pinfunction "GND_2") (pintype "power_in"))
      (node (ref "IC2") (pin "2") (pinfunction "GND_2") (pintype "power_in"))
      (node (ref "IC3") (pin "2") (pinfunction "GND_2") (pintype "power_in"))
      (node (ref "IC4") (pin "2") (pinfunction "GND_2") (pintype "power_in"))
      (node (ref "IC5") (pin "2") (pinfunction "GND_2") (pintype "passive"))
      (node (ref "IC6") (pin "4") (pinfunction "V-_4") (pintype "power_in"))
      (node (ref "LED10") (pin "C") (pinfunction "C_C") (pintype "passive"))
      (node (ref "LED12") (pin "C") (pinfunction "C_C") (pintype "passive"))
      (node (ref "LED14") (pin "C") (pinfunction "C_C") (pintype "passive"))
      (node (ref "LED2") (pin "C") (pinfunction "C_C") (pintype "passive"))
      (node (ref "LED3") (pin "C") (pinfunction "C_C") (pintype "passive"))
      (node (ref "LED4") (pin "C") (pinfunction "C_C") (pintype "passive"))
      (node (ref "LED5") (pin "C") (pinfunction "C_C") (pintype "passive"))
      (node (ref "LED6") (pin "C") (pinfunction "C_C") (pintype "passive"))
      (node (ref "LED7") (pin "C") (pinfunction "C_C") (pintype "passive"))
      (node (ref "LED8") (pin "C") (pinfunction "C_C") (pintype "passive"))
      (node (ref "Q1") (pin "3") (pinfunction "C_3") (pintype "passive"))
      (node (ref "Q2") (pin "3") (pinfunction "C_3") (pintype "passive"))
      (node (ref "Q3") (pin "3") (pinfunction "C_3") (pintype "passive"))
      (node (ref "Q4") (pin "3") (pinfunction "C_3") (pintype "passive"))
      (node (ref "R17") (pin "1") (pinfunction "1_1") (pintype "passive"))
      (node (ref "R18") (pin "1") (pinfunction "1_1") (pintype "passive"))
      (node (ref "R19") (pin "1") (pinfunction "1_1") (pintype "passive"))
      (node (ref "R20") (pin "1") (pinfunction "1_1") (pintype "passive"))
      (node (ref "R21") (pin "1") (pinfunction "1_1") (pintype "passive"))
      (node (ref "R22") (pin "1") (pinfunction "1_1") (pintype "passive"))
      (node (ref "R23") (pin "2") (pinfunction "2_2") (pintype "passive"))
      (node (ref "R25") (pin "2") (pinfunction "2_2") (pintype "passive"))
      (node (ref "R29") (pin "2") (pinfunction "2_2") (pintype "passive"))
      (node (ref "R30") (pin "1") (pinfunction "1_1") (pintype "passive"))
      (node (ref "R31") (pin "2") (pinfunction "2_2") (pintype "passive"))
      (node (ref "R35") (pin "2") (pinfunction "2_2") (pintype "passive"))
      (node (ref "R36") (pin "1") (pinfunction "1_1") (pintype "passive"))
      (node (ref "R37") (pin "2") (pinfunction "2_2") (pintype "passive"))
      (node (ref "R41") (pin "2") (pinfunction "2_2") (pintype "passive"))
      (node (ref "R42") (pin "1") (pinfunction "1_1") (pintype "passive"))
      (node (ref "R43") (pin "2") (pinfunction "2_2") (pintype "passive"))
      (node (ref "R7") (pin "2") (pinfunction "2_2") (pintype "passive"))
      (node (ref "R8") (pin "1") (pinfunction "1_1") (pintype "passive"))
      (node (ref "SV1") (pin "4") (pinfunction "4_4") (pintype "passive"))
      (node (ref "U$1") (pin "GND1") (pinfunction "P$3_GND1") (pintype "bidirectional"))
      (node (ref "U$1") (pin "GND2") (pinfunction "P$2_GND2") (pintype "bidirectional"))
      (node (ref "U$1") (pin "P$21") (pinfunction "GND2_P$21") (pintype "bidirectional"))
      (node (ref "U$1") (pin "P$22") (pinfunction "GND1_P$22") (pintype "bidirectional"))
      (node (ref "U$13") (pin "P$1") (pinfunction "P$1_P$1") (pintype "bidirectional"))
      (node (ref "U$13") (pin "P$2") (pinfunction "P$2_P$2") (pintype "bidirectional"))
      (node (ref "U$13") (pin "P$3") (pinfunction "P$3_P$3") (pintype "bidirectional"))
      (node (ref "U$13") (pin "P$4") (pinfunction "P$4_P$4") (pintype "bidirectional"))
      (node (ref "U$13") (pin "P$5") (pinfunction "P$5_P$5") (pintype "bidirectional"))
      (node (ref "U$13") (pin "P$6") (pinfunction "P$6_P$6") (pintype "bidirectional"))
      (node (ref "U$2") (pin "GND1") (pinfunction "P$3_GND1") (pintype "bidirectional"))
      (node (ref "U$2") (pin "GND2") (pinfunction "P$2_GND2") (pintype "bidirectional"))
      (node (ref "U$2") (pin "P$21") (pinfunction "GND2_P$21") (pintype "bidirectional"))
      (node (ref "U$2") (pin "P$22") (pinfunction "GND1_P$22") (pintype "bidirectional"))
      (node (ref "U$3") (pin "GND1") (pinfunction "P$3_GND1") (pintype "bidirectional"))
      (node (ref "U$3") (pin "GND2") (pinfunction "P$2_GND2") (pintype "bidirectional"))
      (node (ref "U$3") (pin "P$21") (pinfunction "GND2_P$21") (pintype "bidirectional"))
      (node (ref "U$3") (pin "P$22") (pinfunction "GND1_P$22") (pintype "bidirectional"))
      (node (ref "U$4") (pin "GND1") (pinfunction "P$3_GND1") (pintype "bidirectional"))
      (node (ref "U$4") (pin "GND2") (pinfunction "P$2_GND2") (pintype "bidirectional"))
      (node (ref "U$4") (pin "P$21") (pinfunction "GND2_P$21") (pintype "bidirectional"))
      (node (ref "U$4") (pin "P$22") (pinfunction "GND1_P$22") (pintype "bidirectional"))
      (node (ref "U$5") (pin "GND1") (pinfunction "P$3_GND1") (pintype "bidirectional"))
      (node (ref "U$5") (pin "GND2") (pinfunction "P$2_GND2") (pintype "bidirectional"))
      (node (ref "U$5") (pin "P$21") (pinfunction "GND2_P$21") (pintype "bidirectional"))
      (node (ref "U$5") (pin "P$22") (pinfunction "GND1_P$22") (pintype "bidirectional"))
      (node (ref "U$6") (pin "GND1") (pinfunction "P$3_GND1") (pintype "bidirectional"))
      (node (ref "U$6") (pin "GND2") (pinfunction "P$2_GND2") (pintype "bidirectional"))
      (node (ref "U$6") (pin "P$21") (pinfunction "GND2_P$21") (pintype "bidirectional"))
      (node (ref "U$6") (pin "P$22") (pinfunction "GND1_P$22") (pintype "bidirectional"))
      (node (ref "U$9") (pin "LEFTHOLE") (pinfunction "CONTACT_LEFTHOLE") (pintype "bidirectional"))
      (node (ref "U$9") (pin "P$1") (pinfunction "CONTACT_P$1") (pintype "bidirectional"))
      (node (ref "U$9") (pin "P$2") (pinfunction "CONTACT_P$2") (pintype "bidirectional"))
      (node (ref "U$9") (pin "RIGHTHOLE") (pinfunction "CONTACT_RIGHTHOLE") (pintype "bidirectional"))
    )
    (net (code "24") (name "/IC1_IN") (class "Default")
      (node (ref "IC1") (pin "IP+") (pinfunction "IP+_IP+") (pintype "passive"))
      (node (ref "IC1") (pin "IP+@10") (pinfunction "IP+_IP+@10") (pintype "passive"))
      (node (ref "IC1") (pin "IP+@11") (pinfunction "IP+_IP+@11") (pintype "passive"))
      (node (ref "IC1") (pin "IP+@12") (pinfunction "IP+_IP+@12") (pintype "passive"))
      (node (ref "IC1") (pin "IP+@13") (pinfunction "IP+_IP+@13") (pintype "passive"))
      (node (ref "IC1") (pin "IP+@14") (pinfunction "IP+_IP+@14") (pintype "passive"))
      (node (ref "IC1") (pin "IP+@15") (pinfunction "IP+_IP+@15") (pintype "passive"))
      (node (ref "IC1") (pin "IP+@16") (pinfunction "IP+_IP+@16") (pintype "passive"))
      (node (ref "IC1") (pin "IP+@17") (pinfunction "IP+_IP+@17") (pintype "passive"))
      (node (ref "IC1") (pin "IP+@2") (pinfunction "IP+_IP+@2") (pintype "passive"))
      (node (ref "IC1") (pin "IP+@3") (pinfunction "IP+_IP+@3") (pintype "passive"))
      (node (ref "IC1") (pin "IP+@4") (pinfunction "IP+_IP+@4") (pintype "passive"))
      (node (ref "IC1") (pin "IP+@5") (pinfunction "IP+_IP+@5") (pintype "passive"))
      (node (ref "IC1") (pin "IP+@6") (pinfunction "IP+_IP+@6") (pintype "passive"))
      (node (ref "IC1") (pin "IP+@7") (pinfunction "IP+_IP+@7") (pintype "passive"))
      (node (ref "IC1") (pin "IP+@8") (pinfunction "IP+_IP+@8") (pintype "passive"))
      (node (ref "IC1") (pin "IP+@9") (pinfunction "IP+_IP+@9") (pintype "passive"))
      (node (ref "K3") (pin "S") (pinfunction "S_S") (pintype "passive"))
    )
    (net (code "25") (name "/IC2_IN") (class "Default")
      (node (ref "IC2") (pin "IP+") (pinfunction "IP+_IP+") (pintype "passive"))
      (node (ref "IC2") (pin "IP+@10") (pinfunction "IP+_IP+@10") (pintype "passive"))
      (node (ref "IC2") (pin "IP+@11") (pinfunction "IP+_IP+@11") (pintype "passive"))
      (node (ref "IC2") (pin "IP+@12") (pinfunction "IP+_IP+@12") (pintype "passive"))
      (node (ref "IC2") (pin "IP+@13") (pinfunction "IP+_IP+@13") (pintype "passive"))
      (node (ref "IC2") (pin "IP+@14") (pinfunction "IP+_IP+@14") (pintype "passive"))
      (node (ref "IC2") (pin "IP+@15") (pinfunction "IP+_IP+@15") (pintype "passive"))
      (node (ref "IC2") (pin "IP+@16") (pinfunction "IP+_IP+@16") (pintype "passive"))
      (node (ref "IC2") (pin "IP+@17") (pinfunction "IP+_IP+@17") (pintype "passive"))
      (node (ref "IC2") (pin "IP+@2") (pinfunction "IP+_IP+@2") (pintype "passive"))
      (node (ref "IC2") (pin "IP+@3") (pinfunction "IP+_IP+@3") (pintype "passive"))
      (node (ref "IC2") (pin "IP+@4") (pinfunction "IP+_IP+@4") (pintype "passive"))
      (node (ref "IC2") (pin "IP+@5") (pinfunction "IP+_IP+@5") (pintype "passive"))
      (node (ref "IC2") (pin "IP+@6") (pinfunction "IP+_IP+@6") (pintype "passive"))
      (node (ref "IC2") (pin "IP+@7") (pinfunction "IP+_IP+@7") (pintype "passive"))
      (node (ref "IC2") (pin "IP+@8") (pinfunction "IP+_IP+@8") (pintype "passive"))
      (node (ref "IC2") (pin "IP+@9") (pinfunction "IP+_IP+@9") (pintype "passive"))
      (node (ref "K2") (pin "S") (pinfunction "S_S") (pintype "passive"))
    )
    (net (code "26") (name "/IC3_IN") (class "Default")
      (node (ref "IC3") (pin "IP+") (pinfunction "IP+_IP+") (pintype "passive"))
      (node (ref "IC3") (pin "IP+@10") (pinfunction "IP+_IP+@10") (pintype "passive"))
      (node (ref "IC3") (pin "IP+@11") (pinfunction "IP+_IP+@11") (pintype "passive"))
      (node (ref "IC3") (pin "IP+@12") (pinfunction "IP+_IP+@12") (pintype "passive"))
      (node (ref "IC3") (pin "IP+@13") (pinfunction "IP+_IP+@13") (pintype "passive"))
      (node (ref "IC3") (pin "IP+@14") (pinfunction "IP+_IP+@14") (pintype "passive"))
      (node (ref "IC3") (pin "IP+@15") (pinfunction "IP+_IP+@15") (pintype "passive"))
      (node (ref "IC3") (pin "IP+@16") (pinfunction "IP+_IP+@16") (pintype "passive"))
      (node (ref "IC3") (pin "IP+@17") (pinfunction "IP+_IP+@17") (pintype "passive"))
      (node (ref "IC3") (pin "IP+@2") (pinfunction "IP+_IP+@2") (pintype "passive"))
      (node (ref "IC3") (pin "IP+@3") (pinfunction "IP+_IP+@3") (pintype "passive"))
      (node (ref "IC3") (pin "IP+@4") (pinfunction "IP+_IP+@4") (pintype "passive"))
      (node (ref "IC3") (pin "IP+@5") (pinfunction "IP+_IP+@5") (pintype "passive"))
      (node (ref "IC3") (pin "IP+@6") (pinfunction "IP+_IP+@6") (pintype "passive"))
      (node (ref "IC3") (pin "IP+@7") (pinfunction "IP+_IP+@7") (pintype "passive"))
      (node (ref "IC3") (pin "IP+@8") (pinfunction "IP+_IP+@8") (pintype "passive"))
      (node (ref "IC3") (pin "IP+@9") (pinfunction "IP+_IP+@9") (pintype "passive"))
      (node (ref "K1") (pin "S") (pinfunction "S_S") (pintype "passive"))
    )
    (net (code "27") (name "/OUT1") (class "Default")
      (node (ref "IC1") (pin "IP-") (pinfunction "IP-_IP-") (pintype "passive"))
      (node (ref "IC1") (pin "IP-@10") (pinfunction "IP-_IP-@10") (pintype "passive"))
      (node (ref "IC1") (pin "IP-@11") (pinfunction "IP-_IP-@11") (pintype "passive"))
      (node (ref "IC1") (pin "IP-@12") (pinfunction "IP-_IP-@12") (pintype "passive"))
      (node (ref "IC1") (pin "IP-@13") (pinfunction "IP-_IP-@13") (pintype "passive"))
      (node (ref "IC1") (pin "IP-@14") (pinfunction "IP-_IP-@14") (pintype "passive"))
      (node (ref "IC1") (pin "IP-@15") (pinfunction "IP-_IP-@15") (pintype "passive"))
      (node (ref "IC1") (pin "IP-@16") (pinfunction "IP-_IP-@16") (pintype "passive"))
      (node (ref "IC1") (pin "IP-@17") (pinfunction "IP-_IP-@17") (pintype "passive"))
      (node (ref "IC1") (pin "IP-@2") (pinfunction "IP-_IP-@2") (pintype "passive"))
      (node (ref "IC1") (pin "IP-@3") (pinfunction "IP-_IP-@3") (pintype "passive"))
      (node (ref "IC1") (pin "IP-@4") (pinfunction "IP-_IP-@4") (pintype "passive"))
      (node (ref "IC1") (pin "IP-@5") (pinfunction "IP-_IP-@5") (pintype "passive"))
      (node (ref "IC1") (pin "IP-@6") (pinfunction "IP-_IP-@6") (pintype "passive"))
      (node (ref "IC1") (pin "IP-@7") (pinfunction "IP-_IP-@7") (pintype "passive"))
      (node (ref "IC1") (pin "IP-@8") (pinfunction "IP-_IP-@8") (pintype "passive"))
      (node (ref "IC1") (pin "IP-@9") (pinfunction "IP-_IP-@9") (pintype "passive"))
      (node (ref "U$13") (pin "P$12") (pinfunction "P$12_P$12") (pintype "bidirectional"))
    )
    (net (code "28") (name "/OUT2") (class "Default")
      (node (ref "IC2") (pin "IP-") (pinfunction "IP-_IP-") (pintype "passive"))
      (node (ref "IC2") (pin "IP-@10") (pinfunction "IP-_IP-@10") (pintype "passive"))
      (node (ref "IC2") (pin "IP-@11") (pinfunction "IP-_IP-@11") (pintype "passive"))
      (node (ref "IC2") (pin "IP-@12") (pinfunction "IP-_IP-@12") (pintype "passive"))
      (node (ref "IC2") (pin "IP-@13") (pinfunction "IP-_IP-@13") (pintype "passive"))
      (node (ref "IC2") (pin "IP-@14") (pinfunction "IP-_IP-@14") (pintype "passive"))
      (node (ref "IC2") (pin "IP-@15") (pinfunction "IP-_IP-@15") (pintype "passive"))
      (node (ref "IC2") (pin "IP-@16") (pinfunction "IP-_IP-@16") (pintype "passive"))
      (node (ref "IC2") (pin "IP-@17") (pinfunction "IP-_IP-@17") (pintype "passive"))
      (node (ref "IC2") (pin "IP-@2") (pinfunction "IP-_IP-@2") (pintype "passive"))
      (node (ref "IC2") (pin "IP-@3") (pinfunction "IP-_IP-@3") (pintype "passive"))
      (node (ref "IC2") (pin "IP-@4") (pinfunction "IP-_IP-@4") (pintype "passive"))
      (node (ref "IC2") (pin "IP-@5") (pinfunction "IP-_IP-@5") (pintype "passive"))
      (node (ref "IC2") (pin "IP-@6") (pinfunction "IP-_IP-@6") (pintype "passive"))
      (node (ref "IC2") (pin "IP-@7") (pinfunction "IP-_IP-@7") (pintype "passive"))
      (node (ref "IC2") (pin "IP-@8") (pinfunction "IP-_IP-@8") (pintype "passive"))
      (node (ref "IC2") (pin "IP-@9") (pinfunction "IP-_IP-@9") (pintype "passive"))
      (node (ref "U$13") (pin "P$10") (pinfunction "P$10_P$10") (pintype "bidirectional"))
    )
    (net (code "29") (name "/OUT3") (class "Default")
      (node (ref "IC3") (pin "IP-") (pinfunction "IP-_IP-") (pintype "passive"))
      (node (ref "IC3") (pin "IP-@10") (pinfunction "IP-_IP-@10") (pintype "passive"))
      (node (ref "IC3") (pin "IP-@11") (pinfunction "IP-_IP-@11") (pintype "passive"))
      (node (ref "IC3") (pin "IP-@12") (pinfunction "IP-_IP-@12") (pintype "passive"))
      (node (ref "IC3") (pin "IP-@13") (pinfunction "IP-_IP-@13") (pintype "passive"))
      (node (ref "IC3") (pin "IP-@14") (pinfunction "IP-_IP-@14") (pintype "passive"))
      (node (ref "IC3") (pin "IP-@15") (pinfunction "IP-_IP-@15") (pintype "passive"))
      (node (ref "IC3") (pin "IP-@16") (pinfunction "IP-_IP-@16") (pintype "passive"))
      (node (ref "IC3") (pin "IP-@17") (pinfunction "IP-_IP-@17") (pintype "passive"))
      (node (ref "IC3") (pin "IP-@2") (pinfunction "IP-_IP-@2") (pintype "passive"))
      (node (ref "IC3") (pin "IP-@3") (pinfunction "IP-_IP-@3") (pintype "passive"))
      (node (ref "IC3") (pin "IP-@4") (pinfunction "IP-_IP-@4") (pintype "passive"))
      (node (ref "IC3") (pin "IP-@5") (pinfunction "IP-_IP-@5") (pintype "passive"))
      (node (ref "IC3") (pin "IP-@6") (pinfunction "IP-_IP-@6") (pintype "passive"))
      (node (ref "IC3") (pin "IP-@7") (pinfunction "IP-_IP-@7") (pintype "passive"))
      (node (ref "IC3") (pin "IP-@8") (pinfunction "IP-_IP-@8") (pintype "passive"))
      (node (ref "IC3") (pin "IP-@9") (pinfunction "IP-_IP-@9") (pintype "passive"))
      (node (ref "U$13") (pin "P$8") (pinfunction "P$8_P$8") (pintype "bidirectional"))
    )
    (net (code "30") (name "/OUT4") (class "Default")
      (node (ref "IC4") (pin "IP-") (pinfunction "IP-_IP-") (pintype "passive"))
      (node (ref "IC4") (pin "IP-@10") (pinfunction "IP-_IP-@10") (pintype "passive"))
      (node (ref "IC4") (pin "IP-@11") (pinfunction "IP-_IP-@11") (pintype "passive"))
      (node (ref "IC4") (pin "IP-@12") (pinfunction "IP-_IP-@12") (pintype "passive"))
      (node (ref "IC4") (pin "IP-@13") (pinfunction "IP-_IP-@13") (pintype "passive"))
      (node (ref "IC4") (pin "IP-@14") (pinfunction "IP-_IP-@14") (pintype "passive"))
      (node (ref "IC4") (pin "IP-@15") (pinfunction "IP-_IP-@15") (pintype "passive"))
      (node (ref "IC4") (pin "IP-@16") (pinfunction "IP-_IP-@16") (pintype "passive"))
      (node (ref "IC4") (pin "IP-@17") (pinfunction "IP-_IP-@17") (pintype "passive"))
      (node (ref "IC4") (pin "IP-@2") (pinfunction "IP-_IP-@2") (pintype "passive"))
      (node (ref "IC4") (pin "IP-@3") (pinfunction "IP-_IP-@3") (pintype "passive"))
      (node (ref "IC4") (pin "IP-@4") (pinfunction "IP-_IP-@4") (pintype "passive"))
      (node (ref "IC4") (pin "IP-@5") (pinfunction "IP-_IP-@5") (pintype "passive"))
      (node (ref "IC4") (pin "IP-@6") (pinfunction "IP-_IP-@6") (pintype "passive"))
      (node (ref "IC4") (pin "IP-@7") (pinfunction "IP-_IP-@7") (pintype "passive"))
      (node (ref "IC4") (pin "IP-@8") (pinfunction "IP-_IP-@8") (pintype "passive"))
      (node (ref "IC4") (pin "IP-@9") (pinfunction "IP-_IP-@9") (pintype "passive"))
      (node (ref "U$1") (pin "P$15") (pinfunction "VIN2_P$15") (pintype "bidirectional"))
      (node (ref "U$1") (pin "P$16") (pinfunction "VIN1_P$16") (pintype "bidirectional"))
      (node (ref "U$2") (pin "P$15") (pinfunction "VIN2_P$15") (pintype "bidirectional"))
      (node (ref "U$2") (pin "P$16") (pinfunction "VIN1_P$16") (pintype "bidirectional"))
      (node (ref "U$3") (pin "P$15") (pinfunction "VIN2_P$15") (pintype "bidirectional"))
      (node (ref "U$3") (pin "P$16") (pinfunction "VIN1_P$16") (pintype "bidirectional"))
      (node (ref "U$4") (pin "P$15") (pinfunction "VIN2_P$15") (pintype "bidirectional"))
      (node (ref "U$4") (pin "P$16") (pinfunction "VIN1_P$16") (pintype "bidirectional"))
      (node (ref "U$5") (pin "P$15") (pinfunction "VIN2_P$15") (pintype "bidirectional"))
      (node (ref "U$5") (pin "P$16") (pinfunction "VIN1_P$16") (pintype "bidirectional"))
      (node (ref "U$6") (pin "P$15") (pinfunction "VIN2_P$15") (pintype "bidirectional"))
      (node (ref "U$6") (pin "P$16") (pinfunction "VIN1_P$16") (pintype "bidirectional"))
    )
    (net (code "31") (name "/OUTA1") (class "Default")
      (node (ref "U$1") (pin "P$17") (pinfunction "OUTA2_P$17") (pintype "bidirectional"))
      (node (ref "U$1") (pin "P$18") (pinfunction "OUTA1_P$18") (pintype "bidirectional"))
      (node (ref "U$12") (pin "P$3") (pinfunction "P$3_P$3") (pintype "bidirectional"))
    )
    (net (code "32") (name "/OUTA2") (class "Default")
      (node (ref "U$12") (pin "P$2") (pinfunction "P$2_P$2") (pintype "bidirectional"))
      (node (ref "U$2") (pin "P$17") (pinfunction "OUTA2_P$17") (pintype "bidirectional"))
      (node (ref "U$2") (pin "P$18") (pinfunction "OUTA1_P$18") (pintype "bidirectional"))
    )
    (net (code "33") (name "/OUTA3") (class "Default")
      (node (ref "U$12") (pin "P$1") (pinfunction "P$1_P$1") (pintype "bidirectional"))
      (node (ref "U$3") (pin "P$17") (pinfunction "OUTA2_P$17") (pintype "bidirectional"))
      (node (ref "U$3") (pin "P$18") (pinfunction "OUTA1_P$18") (pintype "bidirectional"))
    )
    (net (code "34") (name "/OUTA4") (class "Default")
      (node (ref "U$12") (pin "P$6") (pinfunction "P$6_P$6") (pintype "bidirectional"))
      (node (ref "U$4") (pin "P$17") (pinfunction "OUTA2_P$17") (pintype "bidirectional"))
      (node (ref "U$4") (pin "P$18") (pinfunction "OUTA1_P$18") (pintype "bidirectional"))
    )
    (net (code "35") (name "/OUTA5") (class "Default")
      (node (ref "U$12") (pin "P$5") (pinfunction "P$5_P$5") (pintype "bidirectional"))
      (node (ref "U$5") (pin "P$17") (pinfunction "OUTA2_P$17") (pintype "bidirectional"))
      (node (ref "U$5") (pin "P$18") (pinfunction "OUTA1_P$18") (pintype "bidirectional"))
    )
    (net (code "36") (name "/OUTA6") (class "Default")
      (node (ref "U$12") (pin "P$4") (pinfunction "P$4_P$4") (pintype "bidirectional"))
      (node (ref "U$6") (pin "P$17") (pinfunction "OUTA2_P$17") (pintype "bidirectional"))
      (node (ref "U$6") (pin "P$18") (pinfunction "OUTA1_P$18") (pintype "bidirectional"))
    )
    (net (code "37") (name "/OUTB1") (class "Default")
      (node (ref "U$1") (pin "P$19") (pinfunction "OUTB1_P$19") (pintype "bidirectional"))
      (node (ref "U$1") (pin "P$20") (pinfunction "OUTB2_P$20") (pintype "bidirectional"))
      (node (ref "U$12") (pin "P$7") (pinfunction "P$7_P$7") (pintype "bidirectional"))
    )
    (net (code "38") (name "/OUTB2") (class "Default")
      (node (ref "U$12") (pin "P$8") (pinfunction "P$8_P$8") (pintype "bidirectional"))
      (node (ref "U$2") (pin "P$19") (pinfunction "OUTB1_P$19") (pintype "bidirectional"))
      (node (ref "U$2") (pin "P$20") (pinfunction "OUTB2_P$20") (pintype "bidirectional"))
    )
    (net (code "39") (name "/OUTB3") (class "Default")
      (node (ref "U$12") (pin "P$9") (pinfunction "P$9_P$9") (pintype "bidirectional"))
      (node (ref "U$3") (pin "P$19") (pinfunction "OUTB1_P$19") (pintype "bidirectional"))
      (node (ref "U$3") (pin "P$20") (pinfunction "OUTB2_P$20") (pintype "bidirectional"))
    )
    (net (code "40") (name "/OUTB4") (class "Default")
      (node (ref "U$12") (pin "P$10") (pinfunction "P$10_P$10") (pintype "bidirectional"))
      (node (ref "U$4") (pin "P$19") (pinfunction "OUTB1_P$19") (pintype "bidirectional"))
      (node (ref "U$4") (pin "P$20") (pinfunction "OUTB2_P$20") (pintype "bidirectional"))
    )
    (net (code "41") (name "/OUTB5") (class "Default")
      (node (ref "U$12") (pin "P$11") (pinfunction "P$11_P$11") (pintype "bidirectional"))
      (node (ref "U$5") (pin "P$19") (pinfunction "OUTB1_P$19") (pintype "bidirectional"))
      (node (ref "U$5") (pin "P$20") (pinfunction "OUTB2_P$20") (pintype "bidirectional"))
    )
    (net (code "42") (name "/OUTB6") (class "Default")
      (node (ref "U$12") (pin "P$12") (pinfunction "P$12_P$12") (pintype "bidirectional"))
      (node (ref "U$6") (pin "P$19") (pinfunction "OUTB1_P$19") (pintype "bidirectional"))
      (node (ref "U$6") (pin "P$20") (pinfunction "OUTB2_P$20") (pintype "bidirectional"))
    )
    (net (code "43") (name "/VOLTAGE_REG_OUT") (class "Default")
      (node (ref "B2") (pin "VIN") (pinfunction "VIN_VIN") (pintype "bidirectional"))
      (node (ref "C8") (pin "1") (pinfunction "1_1") (pintype "passive"))
      (node (ref "D1") (pin "C") (pinfunction "C_C") (pintype "passive"))
      (node (ref "D2") (pin "C") (pinfunction "C_C") (pintype "passive"))
      (node (ref "D3") (pin "C") (pinfunction "C_C") (pintype "passive"))
      (node (ref "D4") (pin "C") (pinfunction "C_C") (pintype "passive"))
      (node (ref "IC5") (pin "3") (pinfunction "VO_3") (pintype "passive"))
      (node (ref "K1") (pin "2") (pinfunction "2_2") (pintype "passive"))
      (node (ref "K2") (pin "2") (pinfunction "2_2") (pintype "passive"))
      (node (ref "K3") (pin "2") (pinfunction "2_2") (pintype "passive"))
      (node (ref "OK1") (pin "4") (pinfunction "COL_4") (pintype "passive"))
      (node (ref "OK2") (pin "4") (pinfunction "COL_4") (pintype "passive"))
      (node (ref "OK3") (pin "4") (pinfunction "COL_4") (pintype "passive"))
      (node (ref "OK4") (pin "4") (pinfunction "COL_4") (pintype "passive"))
      (node (ref "R27") (pin "2") (pinfunction "2_2") (pintype "passive"))
      (node (ref "R33") (pin "2") (pinfunction "2_2") (pintype "passive"))
      (node (ref "R39") (pin "2") (pinfunction "2_2") (pintype "passive"))
      (node (ref "R4") (pin "2") (pinfunction "2_2") (pintype "passive"))
      (node (ref "U$11") (pin "COI_V_+") (pinfunction "COIL_V_+_COI_V_+") (pintype "bidirectional"))
    )
    (net (code "44") (name "Net-(B2-PadA0)") (class "Default")
      (node (ref "B2") (pin "A0") (pinfunction "A0_A0") (pintype "bidirectional"))
      (node (ref "C5") (pin "+") (pinfunction "+_+") (pintype "passive"))
      (node (ref "R3") (pin "2") (pinfunction "2_2") (pintype "passive"))
    )
    (net (code "45") (name "Net-(B2-PadA1)") (class "Default")
      (node (ref "B2") (pin "A1") (pinfunction "A1_A1") (pintype "bidirectional"))
      (node (ref "C9") (pin "+") (pinfunction "+_+") (pintype "passive"))
      (node (ref "R5") (pin "2") (pinfunction "2_2") (pintype "passive"))
    )
    (net (code "46") (name "Net-(B2-PadA2)") (class "Default")
      (node (ref "B2") (pin "A2") (pinfunction "A2_A2") (pintype "bidirectional"))
      (node (ref "C3") (pin "+") (pinfunction "+_+") (pintype "passive"))
      (node (ref "R2") (pin "2") (pinfunction "2_2") (pintype "passive"))
    )
    (net (code "47") (name "Net-(B2-PadA3)") (class "Default")
      (node (ref "B2") (pin "A3") (pinfunction "A3_A3") (pintype "bidirectional"))
      (node (ref "C1") (pin "+") (pinfunction "+_+") (pintype "passive"))
      (node (ref "R1") (pin "2") (pinfunction "2_2") (pintype "passive"))
    )
    (net (code "48") (name "Net-(B2-PadSCL)") (class "Default")
      (node (ref "B2") (pin "SCL") (pinfunction "SCL_SCL") (pintype "bidirectional"))
      (node (ref "R15") (pin "2") (pinfunction "2_2") (pintype "passive"))
      (node (ref "SV1") (pin "1") (pinfunction "1_1") (pintype "passive"))
    )
    (net (code "49") (name "Net-(B2-PadSDA)") (class "Default")
      (node (ref "B2") (pin "SDA") (pinfunction "SDA_SDA") (pintype "bidirectional"))
      (node (ref "R14") (pin "2") (pinfunction "2_2") (pintype "passive"))
      (node (ref "SV1") (pin "2") (pinfunction "2_2") (pintype "passive"))
    )
    (net (code "50") (name "Net-(IC1-VOUT)") (class "Default")
      (node (ref "IC1") (pin "3") (pinfunction "VOUT_3") (pintype "output"))
      (node (ref "R1") (pin "1") (pinfunction "1_1") (pintype "passive"))
    )
    (net (code "51") (name "Net-(IC2-VOUT)") (class "Default")
      (node (ref "IC2") (pin "3") (pinfunction "VOUT_3") (pintype "output"))
      (node (ref "R2") (pin "1") (pinfunction "1_1") (pintype "passive"))
    )
    (net (code "52") (name "Net-(IC3-VOUT)") (class "Default")
      (node (ref "IC3") (pin "3") (pinfunction "VOUT_3") (pintype "output"))
      (node (ref "R5") (pin "1") (pinfunction "1_1") (pintype "passive"))
    )
    (net (code "53") (name "Net-(IC4-IP+-PadIP+@10)") (class "Default")
      (node (ref "IC4") (pin "IP+") (pinfunction "IP+_IP+") (pintype "passive"))
      (node (ref "IC4") (pin "IP+@10") (pinfunction "IP+_IP+@10") (pintype "passive"))
      (node (ref "IC4") (pin "IP+@11") (pinfunction "IP+_IP+@11") (pintype "passive"))
      (node (ref "IC4") (pin "IP+@12") (pinfunction "IP+_IP+@12") (pintype "passive"))
      (node (ref "IC4") (pin "IP+@13") (pinfunction "IP+_IP+@13") (pintype "passive"))
      (node (ref "IC4") (pin "IP+@14") (pinfunction "IP+_IP+@14") (pintype "passive"))
      (node (ref "IC4") (pin "IP+@15") (pinfunction "IP+_IP+@15") (pintype "passive"))
      (node (ref "IC4") (pin "IP+@16") (pinfunction "IP+_IP+@16") (pintype "passive"))
      (node (ref "IC4") (pin "IP+@17") (pinfunction "IP+_IP+@17") (pintype "passive"))
      (node (ref "IC4") (pin "IP+@2") (pinfunction "IP+_IP+@2") (pintype "passive"))
      (node (ref "IC4") (pin "IP+@3") (pinfunction "IP+_IP+@3") (pintype "passive"))
      (node (ref "IC4") (pin "IP+@4") (pinfunction "IP+_IP+@4") (pintype "passive"))
      (node (ref "IC4") (pin "IP+@5") (pinfunction "IP+_IP+@5") (pintype "passive"))
      (node (ref "IC4") (pin "IP+@6") (pinfunction "IP+_IP+@6") (pintype "passive"))
      (node (ref "IC4") (pin "IP+@7") (pinfunction "IP+_IP+@7") (pintype "passive"))
      (node (ref "IC4") (pin "IP+@8") (pinfunction "IP+_IP+@8") (pintype "passive"))
      (node (ref "IC4") (pin "IP+@9") (pinfunction "IP+_IP+@9") (pintype "passive"))
      (node (ref "U$11") (pin "NO") (pinfunction "NO_NO") (pintype "bidirectional"))
    )
    (net (code "54") (name "Net-(IC4-VOUT)") (class "Default")
      (node (ref "IC4") (pin "3") (pinfunction "VOUT_3") (pintype "output"))
      (node (ref "R3") (pin "1") (pinfunction "1_1") (pintype "passive"))
    )
    (net (code "55") (name "Net-(IC5-VI)") (class "Default")
      (node (ref "C7") (pin "1") (pinfunction "1_1") (pintype "passive"))
      (node (ref "IC5") (pin "1") (pinfunction "VI_1") (pintype "input"))
      (node (ref "MINISRV11") (pin "RIGHT") (pinfunction "PS2_RIGHT") (pintype "bidirectional"))
      (node (ref "MINISRV11") (pin "RIGHT@1") (pinfunction "PS2_RIGHT@1") (pintype "bidirectional"))
      (node (ref "MINISRV11") (pin "RIGHT@10") (pinfunction "PS2_RIGHT@10") (pintype "bidirectional"))
      (node (ref "MINISRV11") (pin "RIGHT@11") (pinfunction "PS2_RIGHT@11") (pintype "bidirectional"))
      (node (ref "MINISRV11") (pin "RIGHT@12") (pinfunction "PS2_RIGHT@12") (pintype "bidirectional"))
      (node (ref "MINISRV11") (pin "RIGHT@13") (pinfunction "PS2_RIGHT@13") (pintype "bidirectional"))
      (node (ref "MINISRV11") (pin "RIGHT@14") (pinfunction "PS2_RIGHT@14") (pintype "bidirectional"))
      (node (ref "MINISRV11") (pin "RIGHT@15") (pinfunction "PS2_RIGHT@15") (pintype "bidirectional"))
      (node (ref "MINISRV11") (pin "RIGHT@16") (pinfunction "PS2_RIGHT@16") (pintype "bidirectional"))
      (node (ref "MINISRV11") (pin "RIGHT@17") (pinfunction "PS2_RIGHT@17") (pintype "bidirectional"))
      (node (ref "MINISRV11") (pin "RIGHT@18") (pinfunction "PS2_RIGHT@18") (pintype "bidirectional"))
      (node (ref "MINISRV11") (pin "RIGHT@19") (pinfunction "PS2_RIGHT@19") (pintype "bidirectional"))
      (node (ref "MINISRV11") (pin "RIGHT@2") (pinfunction "PS2_RIGHT@2") (pintype "bidirectional"))
      (node (ref "MINISRV11") (pin "RIGHT@20") (pinfunction "PS2_RIGHT@20") (pintype "bidirectional"))
      (node (ref "MINISRV11") (pin "RIGHT@3") (pinfunction "PS2_RIGHT@3") (pintype "bidirectional"))
      (node (ref "MINISRV11") (pin "RIGHT@4") (pinfunction "PS2_RIGHT@4") (pintype "bidirectional"))
      (node (ref "MINISRV11") (pin "RIGHT@5") (pinfunction "PS2_RIGHT@5") (pintype "bidirectional"))
      (node (ref "MINISRV11") (pin "RIGHT@6") (pinfunction "PS2_RIGHT@6") (pintype "bidirectional"))
      (node (ref "MINISRV11") (pin "RIGHT@7") (pinfunction "PS2_RIGHT@7") (pintype "bidirectional"))
      (node (ref "MINISRV11") (pin "RIGHT@8") (pinfunction "PS2_RIGHT@8") (pintype "bidirectional"))
      (node (ref "MINISRV11") (pin "RIGHT@9") (pinfunction "PS2_RIGHT@9") (pintype "bidirectional"))
    )
    (net (code "56") (name "Net-(IC6-+IN)") (class "Default")
      (node (ref "IC6") (pin "3") (pinfunction "+IN_3") (pintype "input"))
      (node (ref "R23") (pin "1") (pinfunction "1_1") (pintype "passive"))
      (node (ref "R24") (pin "2") (pinfunction "2_2") (pintype "passive"))
    )
    (net (code "57") (name "Net-(LED1-PadA)") (class "Default")
      (node (ref "LED1") (pin "A") (pinfunction "A_A") (pintype "passive"))
      (node (ref "R4") (pin "1") (pinfunction "1_1") (pintype "passive"))
    )
    (net (code "58") (name "Net-(LED2-PadA)") (class "Default")
      (node (ref "LED2") (pin "A") (pinfunction "A_A") (pintype "passive"))
      (node (ref "R9") (pin "1") (pinfunction "1_1") (pintype "passive"))
    )
    (net (code "59") (name "Net-(LED3-PadA)") (class "Default")
      (node (ref "LED3") (pin "A") (pinfunction "A_A") (pintype "passive"))
      (node (ref "R10") (pin "1") (pinfunction "1_1") (pintype "passive"))
    )
    (net (code "60") (name "Net-(LED4-PadA)") (class "Default")
      (node (ref "LED4") (pin "A") (pinfunction "A_A") (pintype "passive"))
      (node (ref "R11") (pin "1") (pinfunction "1_1") (pintype "passive"))
    )
    (net (code "61") (name "Net-(LED5-PadA)") (class "Default")
      (node (ref "LED5") (pin "A") (pinfunction "A_A") (pintype "passive"))
      (node (ref "R12") (pin "1") (pinfunction "1_1") (pintype "passive"))
    )
    (net (code "62") (name "Net-(LED6-PadA)") (class "Default")
      (node (ref "LED6") (pin "A") (pinfunction "A_A") (pintype "passive"))
      (node (ref "R13") (pin "1") (pinfunction "1_1") (pintype "passive"))
    )
    (net (code "63") (name "Net-(LED7-PadA)") (class "Default")
      (node (ref "LED7") (pin "A") (pinfunction "A_A") (pintype "passive"))
      (node (ref "R16") (pin "1") (pinfunction "1_1") (pintype "passive"))
    )
    (net (code "64") (name "Net-(LED8-PadA)") (class "Default")
      (node (ref "LED8") (pin "A") (pinfunction "A_A") (pintype "passive"))
      (node (ref "R26") (pin "1") (pinfunction "1_1") (pintype "passive"))
    )
    (net (code "65") (name "Net-(LED9-PadA)") (class "Default")
      (node (ref "LED9") (pin "A") (pinfunction "A_A") (pintype "passive"))
      (node (ref "R27") (pin "1") (pinfunction "1_1") (pintype "passive"))
    )
    (net (code "66") (name "Net-(LED10-PadA)") (class "Default")
      (node (ref "LED10") (pin "A") (pinfunction "A_A") (pintype "passive"))
      (node (ref "R32") (pin "1") (pinfunction "1_1") (pintype "passive"))
    )
    (net (code "67") (name "Net-(LED11-PadA)") (class "Default")
      (node (ref "LED11") (pin "A") (pinfunction "A_A") (pintype "passive"))
      (node (ref "R33") (pin "1") (pinfunction "1_1") (pintype "passive"))
    )
    (net (code "68") (name "Net-(LED12-PadA)") (class "Default")
      (node (ref "LED12") (pin "A") (pinfunction "A_A") (pintype "passive"))
      (node (ref "R38") (pin "1") (pinfunction "1_1") (pintype "passive"))
    )
    (net (code "69") (name "Net-(LED13-PadA)") (class "Default")
      (node (ref "LED13") (pin "A") (pinfunction "A_A") (pintype "passive"))
      (node (ref "R39") (pin "1") (pinfunction "1_1") (pintype "passive"))
    )
    (net (code "70") (name "Net-(LED14-PadA)") (class "Default")
      (node (ref "LED14") (pin "A") (pinfunction "A_A") (pintype "passive"))
      (node (ref "R44") (pin "1") (pinfunction "1_1") (pintype "passive"))
    )
    (net (code "71") (name "Net-(OK1-A)") (class "Default")
      (node (ref "OK1") (pin "1") (pinfunction "A_1") (pintype "passive"))
      (node (ref "R25") (pin "1") (pinfunction "1_1") (pintype "passive"))
      (node (ref "R26") (pin "2") (pinfunction "2_2") (pintype "passive"))
      (node (ref "S10") (pin "1") (pinfunction "1_1") (pintype "passive"))
    )
    (net (code "72") (name "Net-(OK1-C)") (class "Default")
      (node (ref "OK1") (pin "2") (pinfunction "C_2") (pintype "passive"))
      (node (ref "R8") (pin "2") (pinfunction "2_2") (pintype "passive"))
    )
    (net (code "73") (name "Net-(OK1-EMIT)") (class "Default")
      (node (ref "OK1") (pin "3") (pinfunction "EMIT_3") (pintype "passive"))
      (node (ref "R6") (pin "1") (pinfunction "1_1") (pintype "passive"))
      (node (ref "R7") (pin "1") (pinfunction "1_1") (pintype "passive"))
    )
    (net (code "74") (name "Net-(OK2-A)") (class "Default")
      (node (ref "OK2") (pin "1") (pinfunction "A_1") (pintype "passive"))
      (node (ref "R31") (pin "1") (pinfunction "1_1") (pintype "passive"))
      (node (ref "R32") (pin "2") (pinfunction "2_2") (pintype "passive"))
      (node (ref "S9") (pin "1") (pinfunction "1_1") (pintype "passive"))
    )
    (net (code "75") (name "Net-(OK2-C)") (class "Default")
      (node (ref "OK2") (pin "2") (pinfunction "C_2") (pintype "passive"))
      (node (ref "R30") (pin "2") (pinfunction "2_2") (pintype "passive"))
    )
    (net (code "76") (name "Net-(OK2-EMIT)") (class "Default")
      (node (ref "OK2") (pin "3") (pinfunction "EMIT_3") (pintype "passive"))
      (node (ref "R28") (pin "1") (pinfunction "1_1") (pintype "passive"))
      (node (ref "R29") (pin "1") (pinfunction "1_1") (pintype "passive"))
    )
    (net (code "77") (name "Net-(OK3-A)") (class "Default")
      (node (ref "OK3") (pin "1") (pinfunction "A_1") (pintype "passive"))
      (node (ref "R37") (pin "1") (pinfunction "1_1") (pintype "passive"))
      (node (ref "R38") (pin "2") (pinfunction "2_2") (pintype "passive"))
      (node (ref "S2") (pin "1") (pinfunction "1_1") (pintype "passive"))
    )
    (net (code "78") (name "Net-(OK3-C)") (class "Default")
      (node (ref "OK3") (pin "2") (pinfunction "C_2") (pintype "passive"))
      (node (ref "R36") (pin "2") (pinfunction "2_2") (pintype "passive"))
    )
    (net (code "79") (name "Net-(OK3-EMIT)") (class "Default")
      (node (ref "OK3") (pin "3") (pinfunction "EMIT_3") (pintype "passive"))
      (node (ref "R34") (pin "1") (pinfunction "1_1") (pintype "passive"))
      (node (ref "R35") (pin "1") (pinfunction "1_1") (pintype "passive"))
    )
    (net (code "80") (name "Net-(OK4-A)") (class "Default")
      (node (ref "OK4") (pin "1") (pinfunction "A_1") (pintype "passive"))
      (node (ref "R43") (pin "1") (pinfunction "1_1") (pintype "passive"))
      (node (ref "R44") (pin "2") (pinfunction "2_2") (pintype "passive"))
      (node (ref "S1") (pin "1") (pinfunction "1_1") (pintype "passive"))
    )
    (net (code "81") (name "Net-(OK4-C)") (class "Default")
      (node (ref "OK4") (pin "2") (pinfunction "C_2") (pintype "passive"))
      (node (ref "R42") (pin "2") (pinfunction "2_2") (pintype "passive"))
    )
    (net (code "82") (name "Net-(OK4-EMIT)") (class "Default")
      (node (ref "OK4") (pin "3") (pinfunction "EMIT_3") (pintype "passive"))
      (node (ref "R40") (pin "1") (pinfunction "1_1") (pintype "passive"))
      (node (ref "R41") (pin "1") (pinfunction "1_1") (pintype "passive"))
    )
    (net (code "83") (name "Net-(Q1-B)") (class "Default")
      (node (ref "Q1") (pin "1") (pinfunction "B_1") (pintype "passive"))
      (node (ref "R6") (pin "2") (pinfunction "2_2") (pintype "passive"))
    )
    (net (code "84") (name "Net-(Q1-E)") (class "Default")
      (node (ref "D1") (pin "A") (pinfunction "A_A") (pintype "passive"))
      (node (ref "LED1") (pin "C") (pinfunction "C_C") (pintype "passive"))
      (node (ref "Q1") (pin "2") (pinfunction "E_2") (pintype "passive"))
      (node (ref "U$11") (pin "COIL_V_-") (pinfunction "COIL_V_-\\_COIL_V_-") (pintype "bidirectional"))
    )
    (net (code "85") (name "Net-(Q2-B)") (class "Default")
      (node (ref "Q2") (pin "1") (pinfunction "B_1") (pintype "passive"))
      (node (ref "R28") (pin "2") (pinfunction "2_2") (pintype "passive"))
    )
    (net (code "86") (name "Net-(Q3-B)") (class "Default")
      (node (ref "Q3") (pin "1") (pinfunction "B_1") (pintype "passive"))
      (node (ref "R34") (pin "2") (pinfunction "2_2") (pintype "passive"))
    )
    (net (code "87") (name "Net-(Q4-B)") (class "Default")
      (node (ref "Q4") (pin "1") (pinfunction "B_1") (pintype "passive"))
      (node (ref "R40") (pin "2") (pinfunction "2_2") (pintype "passive"))
    )
    (net (code "88") (name "Net-(U$1-P$1)") (class "Default")
      (node (ref "R22") (pin "2") (pinfunction "2_2") (pintype "passive"))
      (node (ref "U$1") (pin "VREF") (pinfunction "P$1_VREF") (pintype "bidirectional"))
    )
    (net (code "89") (name "Net-(U$1-P$6)") (class "Default")
      (node (ref "R16") (pin "2") (pinfunction "2_2") (pintype "passive"))
      (node (ref "S3") (pin "2") (pinfunction "2_2") (pintype "passive"))
      (node (ref "U$1") (pin "SLP") (pinfunction "P$6_SLP") (pintype "bidirectional"))
    )
    (net (code "90") (name "Net-(U$2-P$1)") (class "Default")
      (node (ref "R21") (pin "2") (pinfunction "2_2") (pintype "passive"))
      (node (ref "U$2") (pin "VREF") (pinfunction "P$1_VREF") (pintype "bidirectional"))
    )
    (net (code "91") (name "Net-(U$2-P$6)") (class "Default")
      (node (ref "R13") (pin "2") (pinfunction "2_2") (pintype "passive"))
      (node (ref "S4") (pin "2") (pinfunction "2_2") (pintype "passive"))
      (node (ref "U$2") (pin "SLP") (pinfunction "P$6_SLP") (pintype "bidirectional"))
    )
    (net (code "92") (name "Net-(U$3-P$1)") (class "Default")
      (node (ref "R20") (pin "2") (pinfunction "2_2") (pintype "passive"))
      (node (ref "U$3") (pin "VREF") (pinfunction "P$1_VREF") (pintype "bidirectional"))
    )
    (net (code "93") (name "Net-(U$3-P$6)") (class "Default")
      (node (ref "R9") (pin "2") (pinfunction "2_2") (pintype "passive"))
      (node (ref "S5") (pin "2") (pinfunction "2_2") (pintype "passive"))
      (node (ref "U$3") (pin "SLP") (pinfunction "P$6_SLP") (pintype "bidirectional"))
    )
    (net (code "94") (name "Net-(U$4-P$1)") (class "Default")
      (node (ref "R19") (pin "2") (pinfunction "2_2") (pintype "passive"))
      (node (ref "U$4") (pin "VREF") (pinfunction "P$1_VREF") (pintype "bidirectional"))
    )
    (net (code "95") (name "Net-(U$4-P$6)") (class "Default")
      (node (ref "R10") (pin "2") (pinfunction "2_2") (pintype "passive"))
      (node (ref "S7") (pin "2") (pinfunction "2_2") (pintype "passive"))
      (node (ref "U$4") (pin "SLP") (pinfunction "P$6_SLP") (pintype "bidirectional"))
    )
    (net (code "96") (name "Net-(U$5-P$1)") (class "Default")
      (node (ref "R18") (pin "2") (pinfunction "2_2") (pintype "passive"))
      (node (ref "U$5") (pin "VREF") (pinfunction "P$1_VREF") (pintype "bidirectional"))
    )
    (net (code "97") (name "Net-(U$5-P$6)") (class "Default")
      (node (ref "R11") (pin "2") (pinfunction "2_2") (pintype "passive"))
      (node (ref "S6") (pin "2") (pinfunction "2_2") (pintype "passive"))
      (node (ref "U$5") (pin "SLP") (pinfunction "P$6_SLP") (pintype "bidirectional"))
    )
    (net (code "98") (name "Net-(U$6-P$1)") (class "Default")
      (node (ref "R17") (pin "2") (pinfunction "2_2") (pintype "passive"))
      (node (ref "U$6") (pin "VREF") (pinfunction "P$1_VREF") (pintype "bidirectional"))
    )
    (net (code "99") (name "Net-(U$6-P$6)") (class "Default")
      (node (ref "R12") (pin "2") (pinfunction "2_2") (pintype "passive"))
      (node (ref "S8") (pin "2") (pinfunction "2_2") (pintype "passive"))
      (node (ref "U$6") (pin "SLP") (pinfunction "P$6_SLP") (pintype "bidirectional"))
    )
    (net (code "100") (name "unconnected-(B2-GND-PadGND@2)") (class "Default")
      (node (ref "B2") (pin "GND@2") (pinfunction "GND_GND@2") (pintype "bidirectional"))
    )
    (net (code "101") (name "unconnected-(B2-GND-PadGND@4)") (class "Default")
      (node (ref "B2") (pin "GND@4") (pinfunction "GND_GND@4") (pintype "bidirectional"))
    )
    (net (code "102") (name "unconnected-(B2-PadAREF)") (class "Default")
      (node (ref "B2") (pin "AREF") (pinfunction "AREF_AREF") (pintype "bidirectional"))
    )
    (net (code "103") (name "unconnected-(B2-PadIOREF)") (class "Default")
      (node (ref "B2") (pin "IOREF") (pinfunction "IOREF_IOREF") (pintype "bidirectional"))
    )
    (net (code "104") (name "unconnected-(B2-PadMISO)") (class "Default")
      (node (ref "B2") (pin "MISO") (pinfunction "MISO_MISO") (pintype "bidirectional"))
    )
    (net (code "105") (name "unconnected-(B2-PadMOSI)") (class "Default")
      (node (ref "B2") (pin "MOSI") (pinfunction "MOSI_MOSI") (pintype "bidirectional"))
    )
    (net (code "106") (name "unconnected-(B2-PadSCK)") (class "Default")
      (node (ref "B2") (pin "SCK") (pinfunction "SCK_SCK") (pintype "bidirectional"))
    )
    (net (code "107") (name "unconnected-(B2-PadVCC)") (class "Default")
      (node (ref "B2") (pin "VCC") (pinfunction "VCC_VCC") (pintype "bidirectional"))
    )
    (net (code "108") (name "unconnected-(B2-~{RESET}-PadRESET@1)") (class "Default")
      (node (ref "B2") (pin "RESET@1") (pinfunction "~{RESET}_RESET@1") (pintype "bidirectional"))
    )
    (net (code "109") (name "unconnected-(B2-~{RESET}-PadRESET@2)") (class "Default")
      (node (ref "B2") (pin "RESET@2") (pinfunction "~{RESET}_RESET@2") (pintype "bidirectional"))
    )
    (net (code "110") (name "unconnected-(IC6-ON1-Pad1)") (class "Default")
      (node (ref "IC6") (pin "1") (pinfunction "ON1_1") (pintype "passive"))
    )
    (net (code "111") (name "unconnected-(IC6-ON2-Pad5)") (class "Default")
      (node (ref "IC6") (pin "5") (pinfunction "ON2_5") (pintype "passive"))
    )
    (net (code "112") (name "unconnected-(IC6-OPT-Pad8)") (class "Default")
      (node (ref "IC6") (pin "8") (pinfunction "OPT_8") (pintype "passive"))
    )
    (net (code "113") (name "unconnected-(K1-PadO)") (class "Default")
      (node (ref "K1") (pin "O") (pinfunction "O_O") (pintype "passive"))
    )
    (net (code "114") (name "unconnected-(K2-PadO)") (class "Default")
      (node (ref "K2") (pin "O") (pinfunction "O_O") (pintype "passive"))
    )
    (net (code "115") (name "unconnected-(K3-PadO)") (class "Default")
      (node (ref "K3") (pin "O") (pinfunction "O_O") (pintype "passive"))
    )
    (net (code "116") (name "unconnected-(U$1-P$7-PadFLT)") (class "Default")
      (node (ref "U$1") (pin "FLT") (pinfunction "P$7_FLT") (pintype "bidirectional"))
    )
    (net (code "117") (name "unconnected-(U$1-P$8-PadCS)") (class "Default")
      (node (ref "U$1") (pin "CS") (pinfunction "P$8_CS") (pintype "bidirectional"))
    )
    (net (code "118") (name "unconnected-(U$1-P$9-Pad3V3(OUT))") (class "Default")
      (node (ref "U$1") (pin "3V3(OUT)") (pinfunction "P$9_3V3(OUT)") (pintype "bidirectional"))
    )
    (net (code "119") (name "unconnected-(U$1-P$10-PadVM)") (class "Default")
      (node (ref "U$1") (pin "VM") (pinfunction "P$10_VM") (pintype "bidirectional"))
    )
    (net (code "120") (name "unconnected-(U$2-P$7-PadFLT)") (class "Default")
      (node (ref "U$2") (pin "FLT") (pinfunction "P$7_FLT") (pintype "bidirectional"))
    )
    (net (code "121") (name "unconnected-(U$2-P$8-PadCS)") (class "Default")
      (node (ref "U$2") (pin "CS") (pinfunction "P$8_CS") (pintype "bidirectional"))
    )
    (net (code "122") (name "unconnected-(U$2-P$9-Pad3V3(OUT))") (class "Default")
      (node (ref "U$2") (pin "3V3(OUT)") (pinfunction "P$9_3V3(OUT)") (pintype "bidirectional"))
    )
    (net (code "123") (name "unconnected-(U$2-P$10-PadVM)") (class "Default")
      (node (ref "U$2") (pin "VM") (pinfunction "P$10_VM") (pintype "bidirectional"))
    )
    (net (code "124") (name "unconnected-(U$3-P$7-PadFLT)") (class "Default")
      (node (ref "U$3") (pin "FLT") (pinfunction "P$7_FLT") (pintype "bidirectional"))
    )
    (net (code "125") (name "unconnected-(U$3-P$8-PadCS)") (class "Default")
      (node (ref "U$3") (pin "CS") (pinfunction "P$8_CS") (pintype "bidirectional"))
    )
    (net (code "126") (name "unconnected-(U$3-P$9-Pad3V3(OUT))") (class "Default")
      (node (ref "U$3") (pin "3V3(OUT)") (pinfunction "P$9_3V3(OUT)") (pintype "bidirectional"))
    )
    (net (code "127") (name "unconnected-(U$3-P$10-PadVM)") (class "Default")
      (node (ref "U$3") (pin "VM") (pinfunction "P$10_VM") (pintype "bidirectional"))
    )
    (net (code "128") (name "unconnected-(U$4-P$7-PadFLT)") (class "Default")
      (node (ref "U$4") (pin "FLT") (pinfunction "P$7_FLT") (pintype "bidirectional"))
    )
    (net (code "129") (name "unconnected-(U$4-P$8-PadCS)") (class "Default")
      (node (ref "U$4") (pin "CS") (pinfunction "P$8_CS") (pintype "bidirectional"))
    )
    (net (code "130") (name "unconnected-(U$4-P$9-Pad3V3(OUT))") (class "Default")
      (node (ref "U$4") (pin "3V3(OUT)") (pinfunction "P$9_3V3(OUT)") (pintype "bidirectional"))
    )
    (net (code "131") (name "unconnected-(U$4-P$10-PadVM)") (class "Default")
      (node (ref "U$4") (pin "VM") (pinfunction "P$10_VM") (pintype "bidirectional"))
    )
    (net (code "132") (name "unconnected-(U$5-P$7-PadFLT)") (class "Default")
      (node (ref "U$5") (pin "FLT") (pinfunction "P$7_FLT") (pintype "bidirectional"))
    )
    (net (code "133") (name "unconnected-(U$5-P$8-PadCS)") (class "Default")
      (node (ref "U$5") (pin "CS") (pinfunction "P$8_CS") (pintype "bidirectional"))
    )
    (net (code "134") (name "unconnected-(U$5-P$9-Pad3V3(OUT))") (class "Default")
      (node (ref "U$5") (pin "3V3(OUT)") (pinfunction "P$9_3V3(OUT)") (pintype "bidirectional"))
    )
    (net (code "135") (name "unconnected-(U$5-P$10-PadVM)") (class "Default")
      (node (ref "U$5") (pin "VM") (pinfunction "P$10_VM") (pintype "bidirectional"))
    )
    (net (code "136") (name "unconnected-(U$6-P$7-PadFLT)") (class "Default")
      (node (ref "U$6") (pin "FLT") (pinfunction "P$7_FLT") (pintype "bidirectional"))
    )
    (net (code "137") (name "unconnected-(U$6-P$8-PadCS)") (class "Default")
      (node (ref "U$6") (pin "CS") (pinfunction "P$8_CS") (pintype "bidirectional"))
    )
    (net (code "138") (name "unconnected-(U$6-P$9-Pad3V3(OUT))") (class "Default")
      (node (ref "U$6") (pin "3V3(OUT)") (pinfunction "P$9_3V3(OUT)") (pintype "bidirectional"))
    )
    (net (code "139") (name "unconnected-(U$6-P$10-PadVM)") (class "Default")
      (node (ref "U$6") (pin "VM") (pinfunction "P$10_VM") (pintype "bidirectional"))
    )
    (net (code "140") (name "unconnected-(U$13-PadP$7)") (class "Default")
      (node (ref "U$13") (pin "P$7") (pinfunction "P$7_P$7") (pintype "bidirectional"))
    )
    (net (code "141") (name "unconnected-(U$13-PadP$9)") (class "Default")
      (node (ref "U$13") (pin "P$9") (pinfunction "P$9_P$9") (pintype "bidirectional"))
    )
    (net (code "142") (name "unconnected-(U$13-PadP$11)") (class "Default")
      (node (ref "U$13") (pin "P$11") (pinfunction "P$11_P$11") (pintype "bidirectional"))
    )
  )
)
